# main.net
KiCad netlist of a schematic drawn in EAGLE
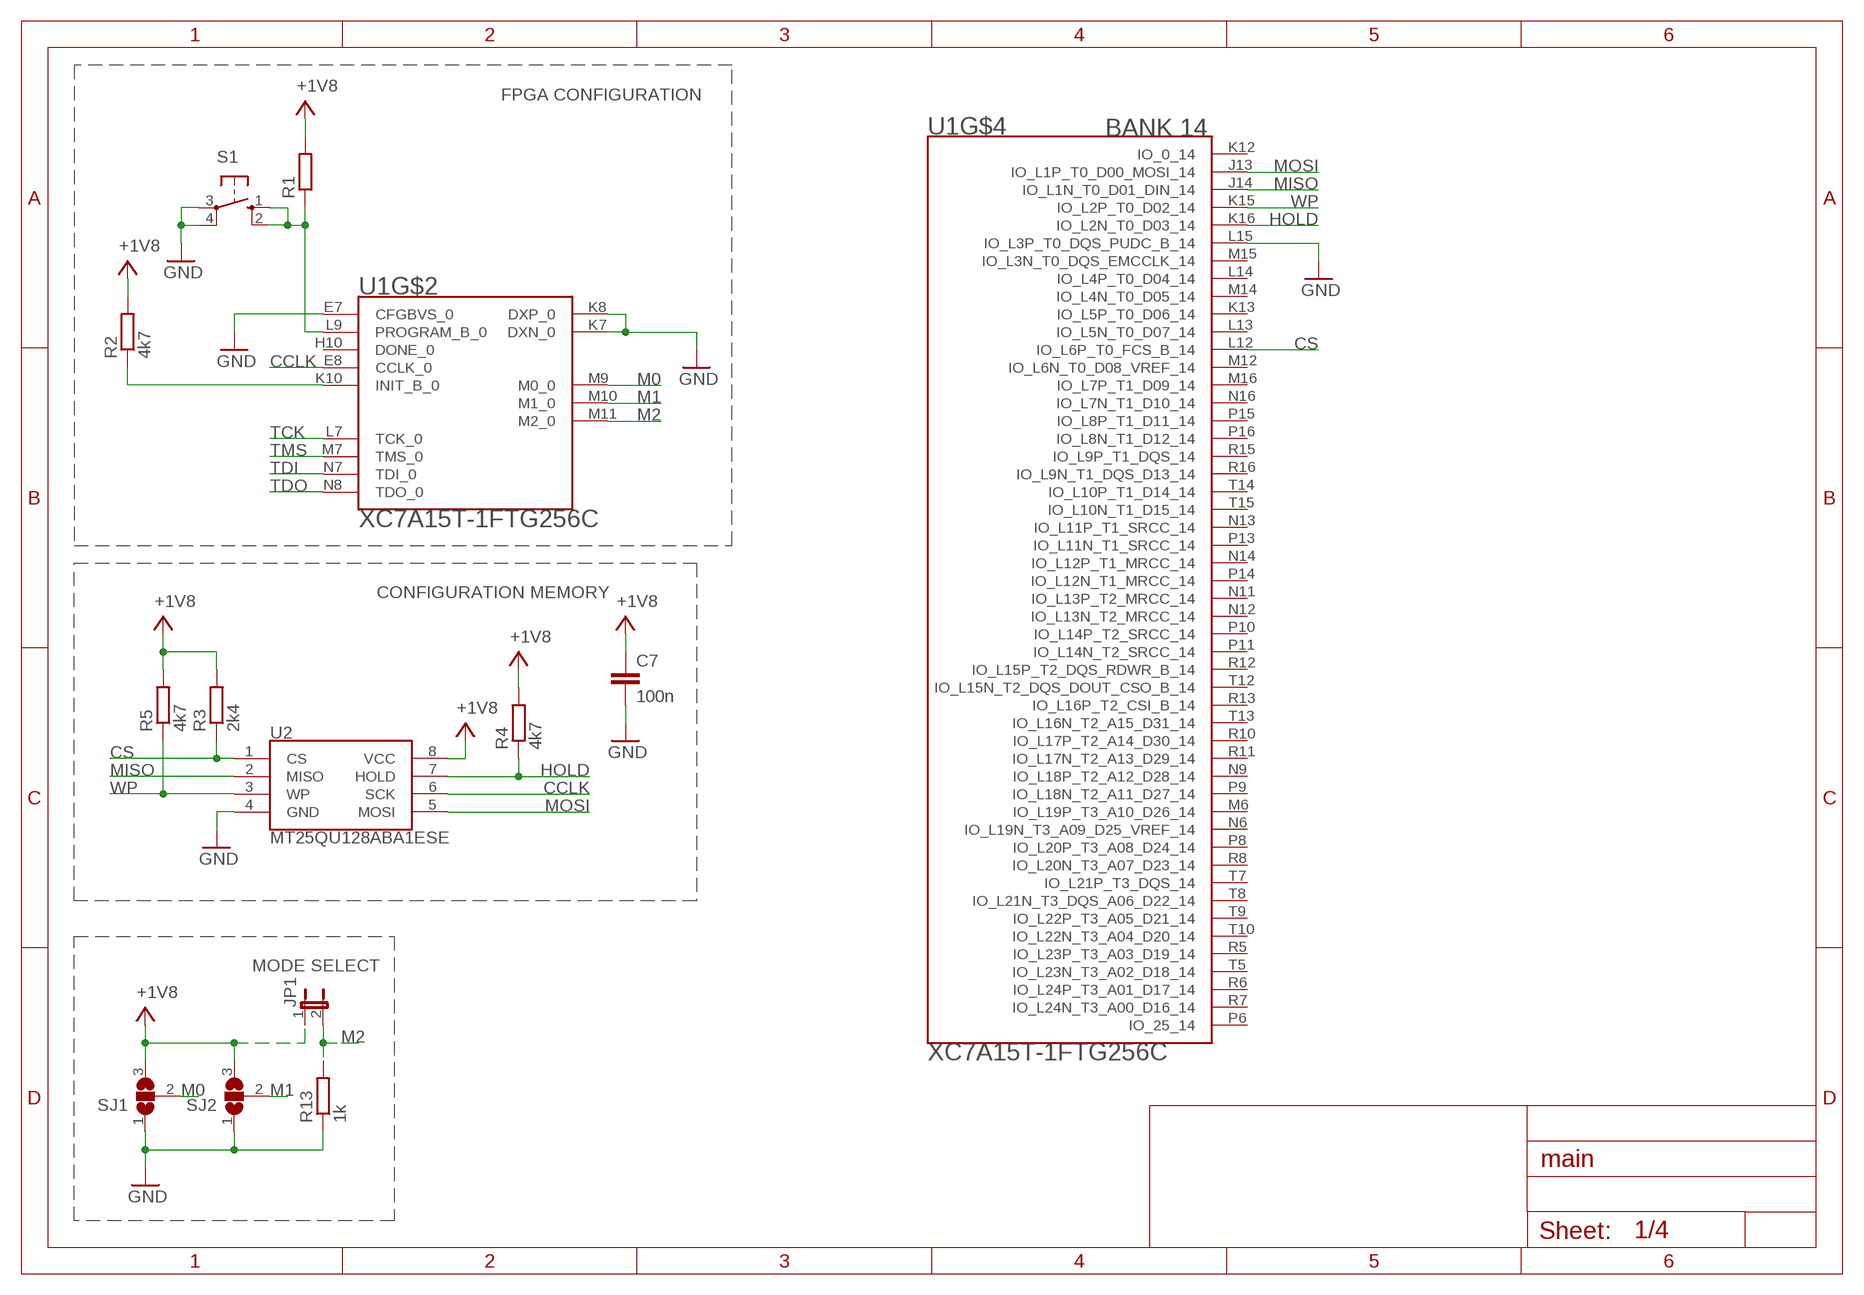
[diagram p0: schematic, sheet 1]
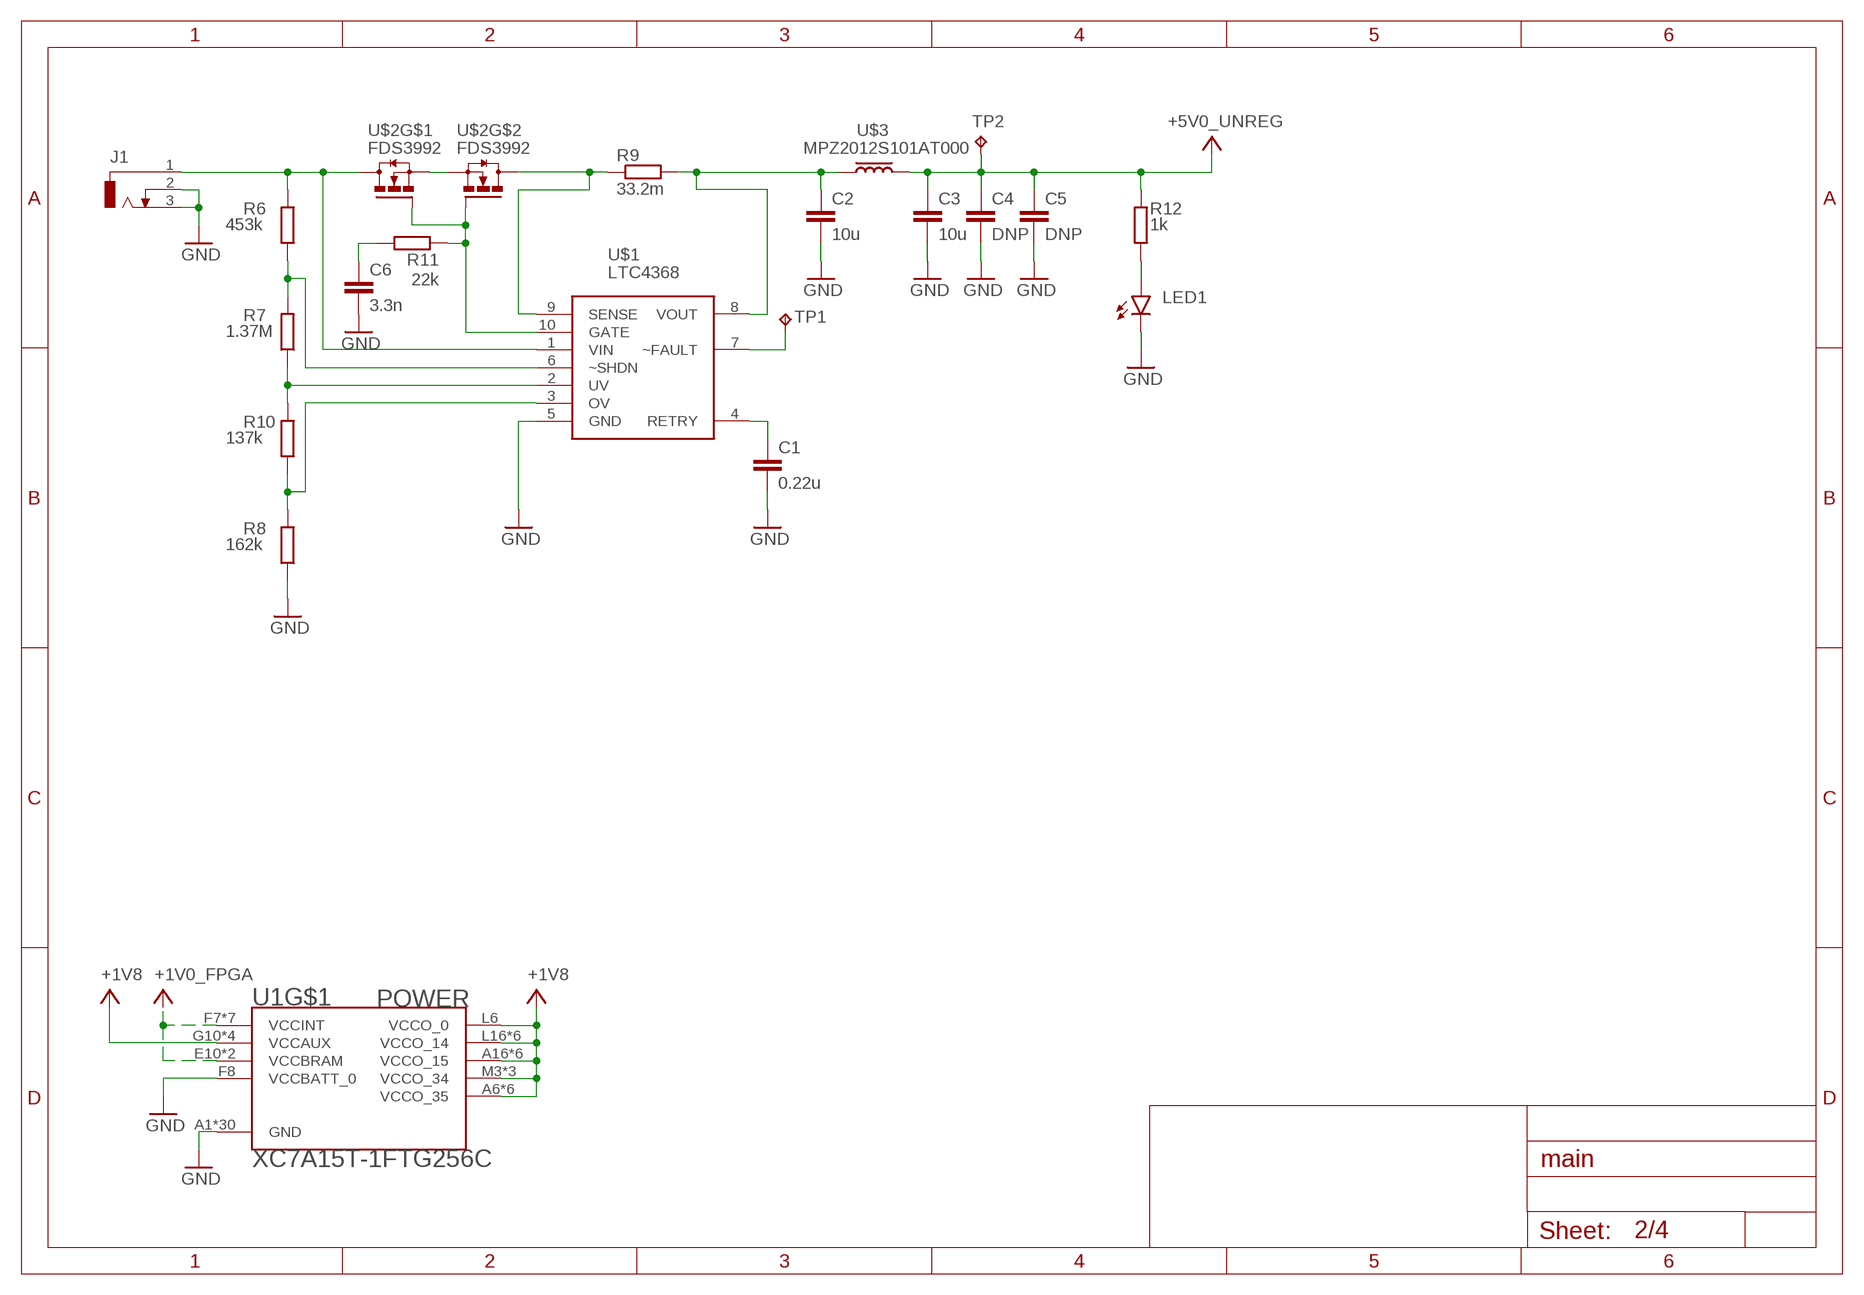
[diagram p1: schematic, sheet 2]
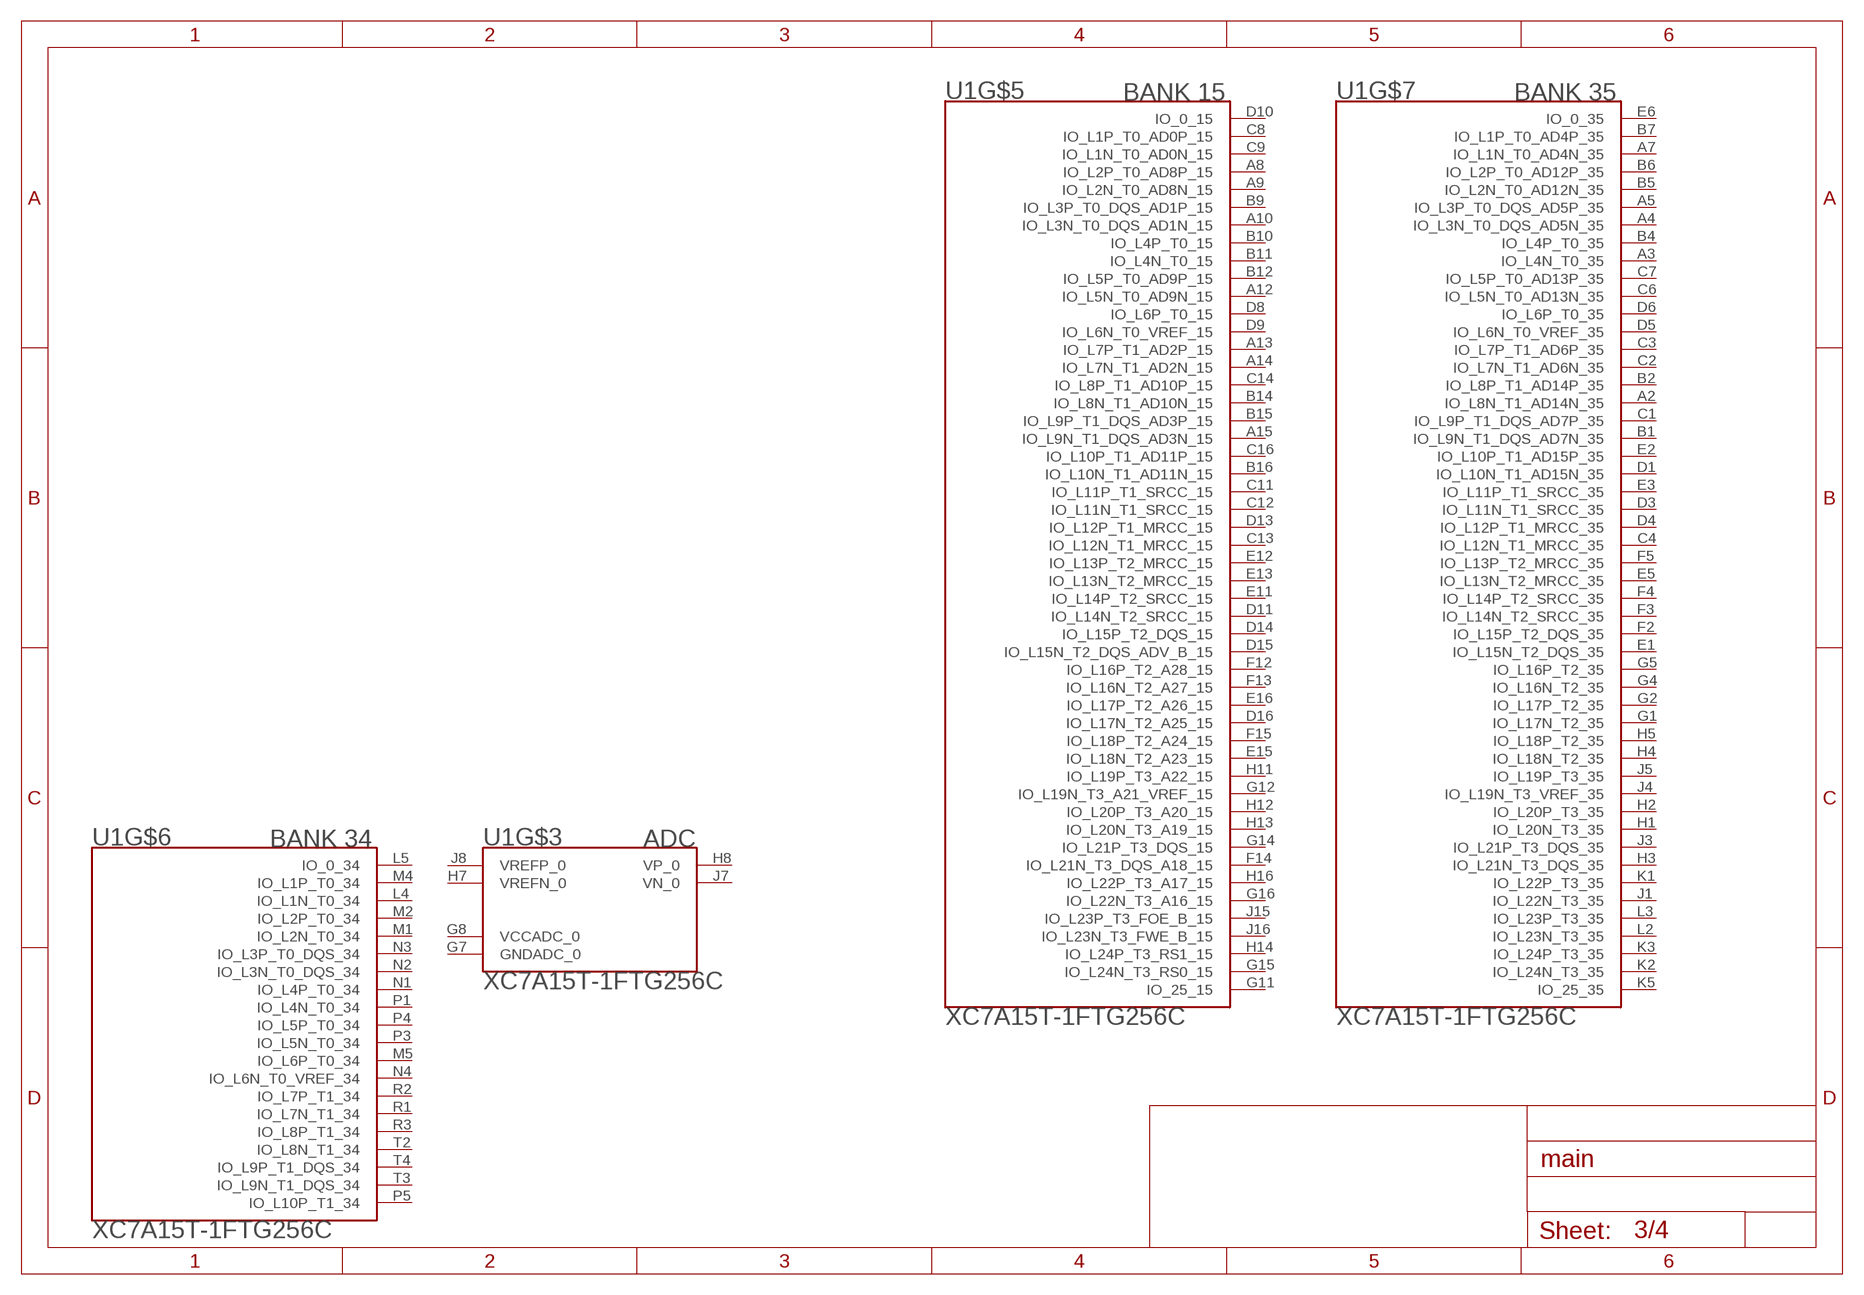
[diagram p2: schematic, sheet 3]
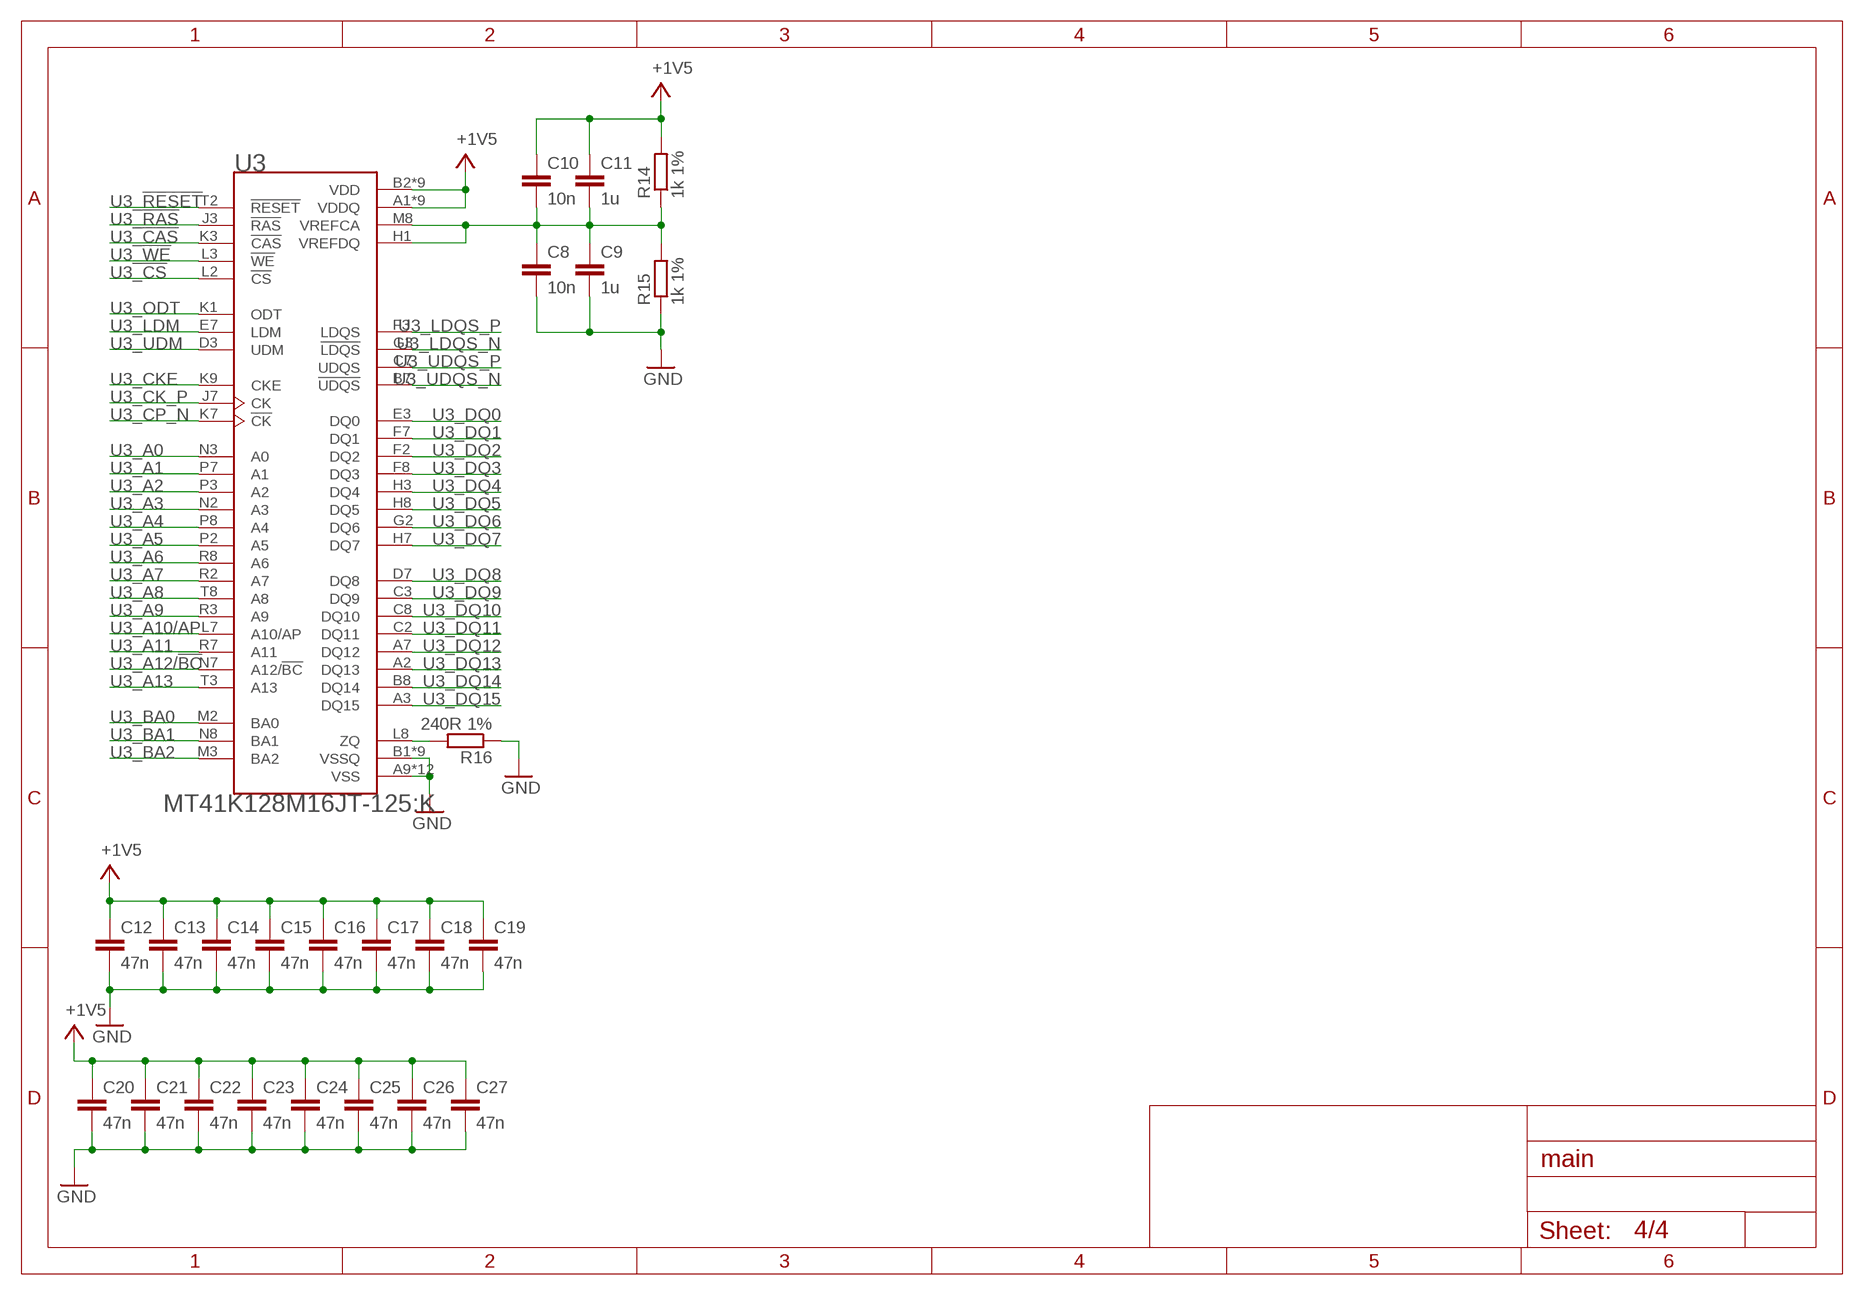
[diagram p3: schematic, sheet 4]

(export (version "E")
  (design (tool "Eeschema 10.0.6"))
  (components
    (comp (ref "C7")
      (value "100n")
      (footprint "eagle-import:C0603")
      (libsource (lib "eagle-import") (part "C-EUC0603"))
    )
    (comp (ref "JP1")
      (value "JP1E")
      (footprint "eagle-import:JP1")
      (libsource (lib "eagle-import") (part "JP1E"))
    )
    (comp (ref "R1")
      (value "R-EU_R0603")
      (footprint "eagle-import:R0603")
      (libsource (lib "eagle-import") (part "R-EU_R0603"))
    )
    (comp (ref "R2")
      (value "4k7")
      (footprint "eagle-import:R0603")
      (libsource (lib "eagle-import") (part "R-EU_R0603"))
    )
    (comp (ref "R3")
      (value "2k4")
      (footprint "eagle-import:R0603")
      (libsource (lib "eagle-import") (part "R-EU_R0603"))
    )
    (comp (ref "R4")
      (value "4k7")
      (footprint "eagle-import:R0603")
      (libsource (lib "eagle-import") (part "R-EU_R0603"))
    )
    (comp (ref "R5")
      (value "4k7")
      (footprint "eagle-import:R0603")
      (libsource (lib "eagle-import") (part "R-EU_R0603"))
    )
    (comp (ref "R13")
      (value "1k")
      (footprint "eagle-import:R0603")
      (libsource (lib "eagle-import") (part "R-EU_R0603"))
    )
    (comp (ref "S1")
      (value "10-XX")
      (footprint "eagle-import:B3F-10XX")
      (fields (field (name "MPN") "B3F-1000"))
      (libsource (lib "eagle-import") (part "10-XX"))
    )
    (comp (ref "SJ1")
      (value "SJ2W")
      (footprint "eagle-import:SJ_2")
      (libsource (lib "eagle-import") (part "SJ2W"))
    )
    (comp (ref "SJ2")
      (value "SJ2W")
      (footprint "eagle-import:SJ_2")
      (libsource (lib "eagle-import") (part "SJ2W"))
    )
    (comp (ref "U1")
      (value "XC7A15T-1FTG256C")
      (footprint "eagle-import:BGA256C100P16X16_1700X1700X155")
      (fields (field (name "MF") "Xilinx Inc."))
      (libsource (lib "eagle-import") (part "XC7A15T-1FTG256C"))
    )
    (comp (ref "U2")
      (value "MT25QU128ABA1ESE")
      (footprint "eagle-import:SO08-EIAJ")
      (libsource (lib "eagle-import") (part "SPI_FLASH-X25XXSMD1"))
    )
    (comp (ref "C8")
      (value "10n")
      (footprint "eagle-import:C0603")
      (libsource (lib "eagle-import") (part "C-EUC0603"))
    )
    (comp (ref "C9")
      (value "1u")
      (footprint "eagle-import:C0603")
      (libsource (lib "eagle-import") (part "C-EUC0603"))
    )
    (comp (ref "C10")
      (value "10n")
      (footprint "eagle-import:C0603")
      (libsource (lib "eagle-import") (part "C-EUC0603"))
    )
    (comp (ref "C11")
      (value "1u")
      (footprint "eagle-import:C0603")
      (libsource (lib "eagle-import") (part "C-EUC0603"))
    )
    (comp (ref "C12")
      (value "47n")
      (footprint "eagle-import:C0603")
      (libsource (lib "eagle-import") (part "C-EUC0603"))
    )
    (comp (ref "C13")
      (value "47n")
      (footprint "eagle-import:C0603")
      (libsource (lib "eagle-import") (part "C-EUC0603"))
    )
    (comp (ref "C14")
      (value "47n")
      (footprint "eagle-import:C0603")
      (libsource (lib "eagle-import") (part "C-EUC0603"))
    )
    (comp (ref "C15")
      (value "47n")
      (footprint "eagle-import:C0603")
      (libsource (lib "eagle-import") (part "C-EUC0603"))
    )
    (comp (ref "C16")
      (value "47n")
      (footprint "eagle-import:C0603")
      (libsource (lib "eagle-import") (part "C-EUC0603"))
    )
    (comp (ref "C17")
      (value "47n")
      (footprint "eagle-import:C0603")
      (libsource (lib "eagle-import") (part "C-EUC0603"))
    )
    (comp (ref "C18")
      (value "47n")
      (footprint "eagle-import:C0603")
      (libsource (lib "eagle-import") (part "C-EUC0603"))
    )
    (comp (ref "C19")
      (value "47n")
      (footprint "eagle-import:C0603")
      (libsource (lib "eagle-import") (part "C-EUC0603"))
    )
    (comp (ref "C20")
      (value "47n")
      (footprint "eagle-import:C0603")
      (libsource (lib "eagle-import") (part "C-EUC0603"))
    )
    (comp (ref "C21")
      (value "47n")
      (footprint "eagle-import:C0603")
      (libsource (lib "eagle-import") (part "C-EUC0603"))
    )
    (comp (ref "C22")
      (value "47n")
      (footprint "eagle-import:C0603")
      (libsource (lib "eagle-import") (part "C-EUC0603"))
    )
    (comp (ref "C23")
      (value "47n")
      (footprint "eagle-import:C0603")
      (libsource (lib "eagle-import") (part "C-EUC0603"))
    )
    (comp (ref "C24")
      (value "47n")
      (footprint "eagle-import:C0603")
      (libsource (lib "eagle-import") (part "C-EUC0603"))
    )
    (comp (ref "C25")
      (value "47n")
      (footprint "eagle-import:C0603")
      (libsource (lib "eagle-import") (part "C-EUC0603"))
    )
    (comp (ref "C26")
      (value "47n")
      (footprint "eagle-import:C0603")
      (libsource (lib "eagle-import") (part "C-EUC0603"))
    )
    (comp (ref "C27")
      (value "47n")
      (footprint "eagle-import:C0603")
      (libsource (lib "eagle-import") (part "C-EUC0603"))
    )
    (comp (ref "R14")
      (value "1k 1%")
      (footprint "eagle-import:R0603")
      (libsource (lib "eagle-import") (part "R-EU_R0603"))
    )
    (comp (ref "R15")
      (value "1k 1%")
      (footprint "eagle-import:R0603")
      (libsource (lib "eagle-import") (part "R-EU_R0603"))
    )
    (comp (ref "R16")
      (value "240R 1%")
      (footprint "eagle-import:R0603")
      (libsource (lib "eagle-import") (part "R-EU_R0603"))
    )
    (comp (ref "U3")
      (value "MT41K128M16JT-125:K")
      (footprint "eagle-import:BGA80P96C6X16_800X1400X110")
      (fields (field (name "MF") "Micron Technology"))
      (libsource (lib "eagle-import") (part "MT41K128M16JT-125{colon}K"))
    )
    (comp (ref "C1")
      (value "0.22u")
      (footprint "eagle-import:C0805")
      (libsource (lib "eagle-import") (part "C-EUC0805"))
    )
    (comp (ref "C2")
      (value "10u")
      (footprint "eagle-import:C0805")
      (libsource (lib "eagle-import") (part "C-EUC0805"))
    )
    (comp (ref "C3")
      (value "10u")
      (footprint "eagle-import:C0805")
      (libsource (lib "eagle-import") (part "C-EUC0805"))
    )
    (comp (ref "C4")
      (value "DNP")
      (footprint "eagle-import:C0805")
      (libsource (lib "eagle-import") (part "C-EUC0805"))
    )
    (comp (ref "C5")
      (value "DNP")
      (footprint "eagle-import:C0805")
      (libsource (lib "eagle-import") (part "C-EUC0805"))
    )
    (comp (ref "C6")
      (value "3.3n")
      (footprint "eagle-import:C0805")
      (libsource (lib "eagle-import") (part "C-EUC0805"))
    )
    (comp (ref "J1")
      (value "DCJ0303")
      (footprint "eagle-import:DCJ0303")
      (libsource (lib "eagle-import") (part "DCJ0303"))
    )
    (comp (ref "LED1")
      (value "LEDCHIP-LED0805")
      (footprint "eagle-import:CHIP-LED0805")
      (libsource (lib "eagle-import") (part "LEDCHIP-LED0805"))
    )
    (comp (ref "R6")
      (value "453k")
      (footprint "eagle-import:R0805")
      (libsource (lib "eagle-import") (part "R-EU_R0805"))
    )
    (comp (ref "R7")
      (value "1.37M")
      (footprint "eagle-import:R0805")
      (libsource (lib "eagle-import") (part "R-EU_R0805"))
    )
    (comp (ref "R8")
      (value "162k")
      (footprint "eagle-import:R0805")
      (libsource (lib "eagle-import") (part "R-EU_R0805"))
    )
    (comp (ref "R9")
      (value "33.2m")
      (footprint "eagle-import:R0805")
      (libsource (lib "eagle-import") (part "R-EU_R0805"))
    )
    (comp (ref "R10")
      (value "137k")
      (footprint "eagle-import:R0805")
      (libsource (lib "eagle-import") (part "R-EU_R0805"))
    )
    (comp (ref "R11")
      (value "22k")
      (footprint "eagle-import:R0805")
      (libsource (lib "eagle-import") (part "R-EU_R0805"))
    )
    (comp (ref "R12")
      (value "1k")
      (footprint "eagle-import:R0805")
      (libsource (lib "eagle-import") (part "R-EU_R0805"))
    )
    (comp (ref "TP1")
      (value "TPB1,27")
      (footprint "eagle-import:B1,27")
      (libsource (lib "eagle-import") (part "TPB1,27"))
    )
    (comp (ref "TP2")
      (value "TPB1,27")
      (footprint "eagle-import:B1,27")
      (libsource (lib "eagle-import") (part "TPB1,27"))
    )
    (comp (ref "U$1")
      (value "LTC4368")
      (footprint "eagle-import:MSOP10")
      (libsource (lib "eagle-import") (part "LTC4368"))
    )
    (comp (ref "U$2")
      (value "FDS3992")
      (footprint "eagle-import:SO-08")
      (libsource (lib "eagle-import") (part "FDS3992"))
    )
    (comp (ref "U$3")
      (value "MPZ2012S101AT000")
      (footprint "eagle-import:FB0805")
      (libsource (lib "eagle-import") (part "MPZ2012S101AT000"))
    )
  )
  (nets
    (net (code "1") (name "+1V0_FPGA") (class "Default")
      (node (ref "U1") (pin "E10") (pinfunction "VCCBRAM_E10") (pintype "power_in"))
      (node (ref "U1") (pin "F11") (pinfunction "VCCBRAM_F11") (pintype "power_in"))
      (node (ref "U1") (pin "F7") (pinfunction "VCCINT_F7") (pintype "power_in"))
      (node (ref "U1") (pin "F9") (pinfunction "VCCINT_F9") (pintype "power_in"))
      (node (ref "U1") (pin "G6") (pinfunction "VCCINT_G6") (pintype "power_in"))
      (node (ref "U1") (pin "H9") (pinfunction "VCCINT_H9") (pintype "power_in"))
      (node (ref "U1") (pin "J6") (pinfunction "VCCINT_J6") (pintype "power_in"))
      (node (ref "U1") (pin "K9") (pinfunction "VCCINT_K9") (pintype "power_in"))
      (node (ref "U1") (pin "L8") (pinfunction "VCCINT_L8") (pintype "power_in"))
    )
    (net (code "2") (name "+1V5") (class "Default")
      (node (ref "C10") (pin "1") (pinfunction "1_1") (pintype "passive"))
      (node (ref "C11") (pin "1") (pinfunction "1_1") (pintype "passive"))
      (node (ref "C12") (pin "1") (pinfunction "1_1") (pintype "passive"))
      (node (ref "C13") (pin "1") (pinfunction "1_1") (pintype "passive"))
      (node (ref "C14") (pin "1") (pinfunction "1_1") (pintype "passive"))
      (node (ref "C15") (pin "1") (pinfunction "1_1") (pintype "passive"))
      (node (ref "C16") (pin "1") (pinfunction "1_1") (pintype "passive"))
      (node (ref "C17") (pin "1") (pinfunction "1_1") (pintype "passive"))
      (node (ref "C18") (pin "1") (pinfunction "1_1") (pintype "passive"))
      (node (ref "C19") (pin "1") (pinfunction "1_1") (pintype "passive"))
      (node (ref "C20") (pin "1") (pinfunction "1_1") (pintype "passive"))
      (node (ref "C21") (pin "1") (pinfunction "1_1") (pintype "passive"))
      (node (ref "C22") (pin "1") (pinfunction "1_1") (pintype "passive"))
      (node (ref "C23") (pin "1") (pinfunction "1_1") (pintype "passive"))
      (node (ref "C24") (pin "1") (pinfunction "1_1") (pintype "passive"))
      (node (ref "C25") (pin "1") (pinfunction "1_1") (pintype "passive"))
      (node (ref "C26") (pin "1") (pinfunction "1_1") (pintype "passive"))
      (node (ref "C27") (pin "1") (pinfunction "1_1") (pintype "passive"))
      (node (ref "R14") (pin "2") (pinfunction "2_2") (pintype "passive"))
      (node (ref "U3") (pin "A1") (pinfunction "VDDQ_A1") (pintype "power_in"))
      (node (ref "U3") (pin "A8") (pinfunction "VDDQ_A8") (pintype "power_in"))
      (node (ref "U3") (pin "B2") (pinfunction "VDD_B2") (pintype "power_in"))
      (node (ref "U3") (pin "C1") (pinfunction "VDDQ_C1") (pintype "power_in"))
      (node (ref "U3") (pin "C9") (pinfunction "VDDQ_C9") (pintype "power_in"))
      (node (ref "U3") (pin "D2") (pinfunction "VDDQ_D2") (pintype "power_in"))
      (node (ref "U3") (pin "D9") (pinfunction "VDD_D9") (pintype "power_in"))
      (node (ref "U3") (pin "E9") (pinfunction "VDDQ_E9") (pintype "power_in"))
      (node (ref "U3") (pin "F1") (pinfunction "VDDQ_F1") (pintype "power_in"))
      (node (ref "U3") (pin "G7") (pinfunction "VDD_G7") (pintype "power_in"))
      (node (ref "U3") (pin "H2") (pinfunction "VDDQ_H2") (pintype "power_in"))
      (node (ref "U3") (pin "H9") (pinfunction "VDDQ_H9") (pintype "power_in"))
      (node (ref "U3") (pin "K2") (pinfunction "VDD_K2") (pintype "power_in"))
      (node (ref "U3") (pin "K8") (pinfunction "VDD_K8") (pintype "power_in"))
      (node (ref "U3") (pin "N1") (pinfunction "VDD_N1") (pintype "power_in"))
      (node (ref "U3") (pin "N9") (pinfunction "VDD_N9") (pintype "power_in"))
      (node (ref "U3") (pin "R1") (pinfunction "VDD_R1") (pintype "power_in"))
      (node (ref "U3") (pin "R9") (pinfunction "VDD_R9") (pintype "power_in"))
    )
    (net (code "3") (name "+1V8") (class "Default")
      (node (ref "C7") (pin "1") (pinfunction "1_1") (pintype "passive"))
      (node (ref "JP1") (pin "1") (pinfunction "1_1") (pintype "passive"))
      (node (ref "R1") (pin "2") (pinfunction "2_2") (pintype "passive"))
      (node (ref "R2") (pin "2") (pinfunction "2_2") (pintype "passive"))
      (node (ref "R3") (pin "2") (pinfunction "2_2") (pintype "passive"))
      (node (ref "R4") (pin "2") (pinfunction "2_2") (pintype "passive"))
      (node (ref "R5") (pin "2") (pinfunction "2_2") (pintype "passive"))
      (node (ref "SJ1") (pin "3") (pinfunction "3_3") (pintype "passive"))
      (node (ref "SJ2") (pin "3") (pinfunction "3_3") (pintype "passive"))
      (node (ref "U1") (pin "A16") (pinfunction "VCCO_15_A16") (pintype "power_in"))
      (node (ref "U1") (pin "A6") (pinfunction "VCCO_35_A6") (pintype "power_in"))
      (node (ref "U1") (pin "B13") (pinfunction "VCCO_15_B13") (pintype "power_in"))
      (node (ref "U1") (pin "B3") (pinfunction "VCCO_35_B3") (pintype "power_in"))
      (node (ref "U1") (pin "C10") (pinfunction "VCCO_15_C10") (pintype "power_in"))
      (node (ref "U1") (pin "D7") (pinfunction "VCCO_35_D7") (pintype "power_in"))
      (node (ref "U1") (pin "E14") (pinfunction "VCCO_15_E14") (pintype "power_in"))
      (node (ref "U1") (pin "E4") (pinfunction "VCCO_35_E4") (pintype "power_in"))
      (node (ref "U1") (pin "F1") (pinfunction "VCCO_35_F1") (pintype "power_in"))
      (node (ref "U1") (pin "G10") (pinfunction "VCCAUX_G10") (pintype "power_in"))
      (node (ref "U1") (pin "H15") (pinfunction "VCCO_15_H15") (pintype "power_in"))
      (node (ref "U1") (pin "J10") (pinfunction "VCCAUX_J10") (pintype "power_in"))
      (node (ref "U1") (pin "J12") (pinfunction "VCCO_15_J12") (pintype "power_in"))
      (node (ref "U1") (pin "J2") (pinfunction "VCCO_35_J2") (pintype "power_in"))
      (node (ref "U1") (pin "K11") (pinfunction "VCCAUX_K11") (pintype "power_in"))
      (node (ref "U1") (pin "L10") (pinfunction "VCCAUX_L10") (pintype "power_in"))
      (node (ref "U1") (pin "L16") (pinfunction "VCCO_14_L16") (pintype "power_in"))
      (node (ref "U1") (pin "L6") (pinfunction "VCCO_0_L6") (pintype "power_in"))
      (node (ref "U1") (pin "M13") (pinfunction "VCCO_14_M13") (pintype "power_in"))
      (node (ref "U1") (pin "M3") (pinfunction "VCCO_34_M3") (pintype "power_in"))
      (node (ref "U1") (pin "N10") (pinfunction "VCCO_14_N10") (pintype "power_in"))
      (node (ref "U1") (pin "P7") (pinfunction "VCCO_14_P7") (pintype "power_in"))
      (node (ref "U1") (pin "R14") (pinfunction "VCCO_14_R14") (pintype "power_in"))
      (node (ref "U1") (pin "R4") (pinfunction "VCCO_34_R4") (pintype "power_in"))
      (node (ref "U1") (pin "T1") (pinfunction "VCCO_34_T1") (pintype "power_in"))
      (node (ref "U1") (pin "T11") (pinfunction "VCCO_14_T11") (pintype "power_in"))
      (node (ref "U2") (pin "8") (pinfunction "VCC_8") (pintype "power_in"))
    )
    (net (code "4") (name "+5V0_UNREG") (class "Default")
      (node (ref "C3") (pin "1") (pinfunction "1_1") (pintype "passive"))
      (node (ref "C4") (pin "1") (pinfunction "1_1") (pintype "passive"))
      (node (ref "C5") (pin "1") (pinfunction "1_1") (pintype "passive"))
      (node (ref "R12") (pin "2") (pinfunction "2_2") (pintype "passive"))
      (node (ref "TP2") (pin "TP") (pinfunction "TP_TP") (pintype "input"))
      (node (ref "U$3") (pin "2") (pinfunction "2_2") (pintype "passive"))
    )
    (net (code "5") (name "CCLK") (class "Default")
      (node (ref "U1") (pin "E8") (pinfunction "CCLK_0_E8") (pintype "bidirectional"))
      (node (ref "U2") (pin "6") (pinfunction "SCK_6") (pintype "bidirectional"))
    )
    (net (code "6") (name "CS") (class "Default")
      (node (ref "R3") (pin "1") (pinfunction "1_1") (pintype "passive"))
      (node (ref "U1") (pin "L12") (pinfunction "IO_L6P_T0_FCS_B_14_L12") (pintype "bidirectional"))
      (node (ref "U2") (pin "1") (pinfunction "CS_1") (pintype "bidirectional"))
    )
    (net (code "7") (name "GND") (class "Default")
      (node (ref "C1") (pin "2") (pinfunction "2_2") (pintype "passive"))
      (node (ref "C12") (pin "2") (pinfunction "2_2") (pintype "passive"))
      (node (ref "C13") (pin "2") (pinfunction "2_2") (pintype "passive"))
      (node (ref "C14") (pin "2") (pinfunction "2_2") (pintype "passive"))
      (node (ref "C15") (pin "2") (pinfunction "2_2") (pintype "passive"))
      (node (ref "C16") (pin "2") (pinfunction "2_2") (pintype "passive"))
      (node (ref "C17") (pin "2") (pinfunction "2_2") (pintype "passive"))
      (node (ref "C18") (pin "2") (pinfunction "2_2") (pintype "passive"))
      (node (ref "C19") (pin "2") (pinfunction "2_2") (pintype "passive"))
      (node (ref "C2") (pin "2") (pinfunction "2_2") (pintype "passive"))
      (node (ref "C20") (pin "2") (pinfunction "2_2") (pintype "passive"))
      (node (ref "C21") (pin "2") (pinfunction "2_2") (pintype "passive"))
      (node (ref "C22") (pin "2") (pinfunction "2_2") (pintype "passive"))
      (node (ref "C23") (pin "2") (pinfunction "2_2") (pintype "passive"))
      (node (ref "C24") (pin "2") (pinfunction "2_2") (pintype "passive"))
      (node (ref "C25") (pin "2") (pinfunction "2_2") (pintype "passive"))
      (node (ref "C26") (pin "2") (pinfunction "2_2") (pintype "passive"))
      (node (ref "C27") (pin "2") (pinfunction "2_2") (pintype "passive"))
      (node (ref "C3") (pin "2") (pinfunction "2_2") (pintype "passive"))
      (node (ref "C4") (pin "2") (pinfunction "2_2") (pintype "passive"))
      (node (ref "C5") (pin "2") (pinfunction "2_2") (pintype "passive"))
      (node (ref "C6") (pin "2") (pinfunction "2_2") (pintype "passive"))
      (node (ref "C7") (pin "2") (pinfunction "2_2") (pintype "passive"))
      (node (ref "C8") (pin "2") (pinfunction "2_2") (pintype "passive"))
      (node (ref "C9") (pin "2") (pinfunction "2_2") (pintype "passive"))
      (node (ref "J1") (pin "2") (pinfunction "2_2") (pintype "passive"))
      (node (ref "J1") (pin "3") (pinfunction "3_3") (pintype "passive"))
      (node (ref "LED1") (pin "C") (pinfunction "C_C") (pintype "passive"))
      (node (ref "R13") (pin "1") (pinfunction "1_1") (pintype "passive"))
      (node (ref "R15") (pin "1") (pinfunction "1_1") (pintype "passive"))
      (node (ref "R16") (pin "1") (pinfunction "1_1") (pintype "passive"))
      (node (ref "R8") (pin "1") (pinfunction "1_1") (pintype "passive"))
      (node (ref "S1") (pin "3") (pinfunction "P_3") (pintype "passive"))
      (node (ref "S1") (pin "4") (pinfunction "P1_4") (pintype "passive"))
      (node (ref "SJ1") (pin "1") (pinfunction "1_1") (pintype "passive"))
      (node (ref "SJ2") (pin "1") (pinfunction "1_1") (pintype "passive"))
      (node (ref "U$1") (pin "5") (pinfunction "GND_5") (pintype "bidirectional"))
      (node (ref "U1") (pin "A1") (pinfunction "GND_A1") (pintype "power_in"))
      (node (ref "U1") (pin "A11") (pinfunction "GND_A11") (pintype "power_in"))
      (node (ref "U1") (pin "B8") (pinfunction "GND_B8") (pintype "power_in"))
      (node (ref "U1") (pin "C15") (pinfunction "GND_C15") (pintype "power_in"))
      (node (ref "U1") (pin "C5") (pinfunction "GND_C5") (pintype "power_in"))
      (node (ref "U1") (pin "D12") (pinfunction "GND_D12") (pintype "power_in"))
      (node (ref "U1") (pin "D2") (pinfunction "GND_D2") (pintype "power_in"))
      (node (ref "U1") (pin "E7") (pinfunction "CFGBVS_0_E7") (pintype "input"))
      (node (ref "U1") (pin "E9") (pinfunction "GND_E9") (pintype "power_in"))
      (node (ref "U1") (pin "F10") (pinfunction "GND_F10") (pintype "power_in"))
      (node (ref "U1") (pin "F16") (pinfunction "GND_F16") (pintype "power_in"))
      (node (ref "U1") (pin "F6") (pinfunction "GND_F6") (pintype "power_in"))
      (node (ref "U1") (pin "F8") (pinfunction "VCCBATT_0_F8") (pintype "power_in"))
      (node (ref "U1") (pin "G13") (pinfunction "GND_G13") (pintype "power_in"))
      (node (ref "U1") (pin "G3") (pinfunction "GND_G3") (pintype "power_in"))
      (node (ref "U1") (pin "G9") (pinfunction "GND_G9") (pintype "power_in"))
      (node (ref "U1") (pin "H6") (pinfunction "GND_H6") (pintype "power_in"))
      (node (ref "U1") (pin "J11") (pinfunction "GND_J11") (pintype "power_in"))
      (node (ref "U1") (pin "J9") (pinfunction "GND_J9") (pintype "power_in"))
      (node (ref "U1") (pin "K14") (pinfunction "GND_K14") (pintype "power_in"))
      (node (ref "U1") (pin "K4") (pinfunction "GND_K4") (pintype "power_in"))
      (node (ref "U1") (pin "K6") (pinfunction "GND_K6") (pintype "power_in"))
      (node (ref "U1") (pin "K7") (pinfunction "DXN_0_K7") (pintype "input"))
      (node (ref "U1") (pin "K8") (pinfunction "DXP_0_K8") (pintype "input"))
      (node (ref "U1") (pin "L1") (pinfunction "GND_L1") (pintype "power_in"))
      (node (ref "U1") (pin "L11") (pinfunction "GND_L11") (pintype "power_in"))
      (node (ref "U1") (pin "L15") (pinfunction "IO_L3P_T0_DQS_PUDC_B_14_L15") (pintype "bidirectional"))
      (node (ref "U1") (pin "M8") (pinfunction "GND_M8") (pintype "power_in"))
      (node (ref "U1") (pin "N15") (pinfunction "GND_N15") (pintype "power_in"))
      (node (ref "U1") (pin "N5") (pinfunction "GND_N5") (pintype "power_in"))
      (node (ref "U1") (pin "P12") (pinfunction "GND_P12") (pintype "power_in"))
      (node (ref "U1") (pin "P2") (pinfunction "GND_P2") (pintype "power_in"))
      (node (ref "U1") (pin "R9") (pinfunction "GND_R9") (pintype "power_in"))
      (node (ref "U1") (pin "T16") (pinfunction "GND_T16") (pintype "power_in"))
      (node (ref "U1") (pin "T6") (pinfunction "GND_T6") (pintype "power_in"))
      (node (ref "U2") (pin "4") (pinfunction "GND_4") (pintype "power_in"))
      (node (ref "U3") (pin "A9") (pinfunction "VSS_A9") (pintype "passive"))
      (node (ref "U3") (pin "B1") (pinfunction "VSSQ_B1") (pintype "passive"))
      (node (ref "U3") (pin "B3") (pinfunction "VSS_B3") (pintype "passive"))
      (node (ref "U3") (pin "B9") (pinfunction "VSSQ_B9") (pintype "passive"))
      (node (ref "U3") (pin "D1") (pinfunction "VSSQ_D1") (pintype "passive"))
      (node (ref "U3") (pin "D8") (pinfunction "VSSQ_D8") (pintype "passive"))
      (node (ref "U3") (pin "E1") (pinfunction "VSS_E1") (pintype "passive"))
      (node (ref "U3") (pin "E2") (pinfunction "VSSQ_E2") (pintype "passive"))
      (node (ref "U3") (pin "E8") (pinfunction "VSSQ_E8") (pintype "passive"))
      (node (ref "U3") (pin "F9") (pinfunction "VSSQ_F9") (pintype "passive"))
      (node (ref "U3") (pin "G1") (pinfunction "VSSQ_G1") (pintype "passive"))
      (node (ref "U3") (pin "G8") (pinfunction "VSS_G8") (pintype "passive"))
      (node (ref "U3") (pin "G9") (pinfunction "VSSQ_G9") (pintype "passive"))
      (node (ref "U3") (pin "J2") (pinfunction "VSS_J2") (pintype "passive"))
      (node (ref "U3") (pin "J8") (pinfunction "VSS_J8") (pintype "passive"))
      (node (ref "U3") (pin "M1") (pinfunction "VSS_M1") (pintype "passive"))
      (node (ref "U3") (pin "M9") (pinfunction "VSS_M9") (pintype "passive"))
      (node (ref "U3") (pin "P1") (pinfunction "VSS_P1") (pintype "passive"))
      (node (ref "U3") (pin "P9") (pinfunction "VSS_P9") (pintype "passive"))
      (node (ref "U3") (pin "T1") (pinfunction "VSS_T1") (pintype "passive"))
      (node (ref "U3") (pin "T9") (pinfunction "VSS_T9") (pintype "passive"))
    )
    (net (code "8") (name "GNDADC_0") (class "Default")
      (node (ref "U1") (pin "G7") (pinfunction "GNDADC_0_G7") (pintype "power_in"))
    )
    (net (code "9") (name "HOLD") (class "Default")
      (node (ref "R4") (pin "1") (pinfunction "1_1") (pintype "passive"))
      (node (ref "U1") (pin "K16") (pinfunction "IO_L2N_T0_D03_14_K16") (pintype "bidirectional"))
      (node (ref "U2") (pin "7") (pinfunction "HOLD_7") (pintype "bidirectional"))
    )
    (net (code "10") (name "M0") (class "Default")
      (node (ref "SJ1") (pin "2") (pinfunction "2_2") (pintype "passive"))
      (node (ref "U1") (pin "M9") (pinfunction "M0_0_M9") (pintype "input"))
    )
    (net (code "11") (name "M1") (class "Default")
      (node (ref "SJ2") (pin "2") (pinfunction "2_2") (pintype "passive"))
      (node (ref "U1") (pin "M10") (pinfunction "M1_0_M10") (pintype "input"))
    )
    (net (code "12") (name "M2") (class "Default")
      (node (ref "JP1") (pin "2") (pinfunction "2_2") (pintype "passive"))
      (node (ref "R13") (pin "2") (pinfunction "2_2") (pintype "passive"))
      (node (ref "U1") (pin "M11") (pinfunction "M2_0_M11") (pintype "input"))
    )
    (net (code "13") (name "MISO") (class "Default")
      (node (ref "U1") (pin "J14") (pinfunction "IO_L1N_T0_D01_DIN_14_J14") (pintype "bidirectional"))
      (node (ref "U2") (pin "2") (pinfunction "MISO_2") (pintype "bidirectional"))
    )
    (net (code "14") (name "MOSI") (class "Default")
      (node (ref "U1") (pin "J13") (pinfunction "IO_L1P_T0_D00_MOSI_14_J13") (pintype "bidirectional"))
      (node (ref "U2") (pin "5") (pinfunction "MOSI_5") (pintype "bidirectional"))
    )
    (net (code "15") (name "Net-(C6-Pad1)") (class "Default")
      (node (ref "C6") (pin "1") (pinfunction "1_1") (pintype "passive"))
      (node (ref "R11") (pin "2") (pinfunction "2_2") (pintype "passive"))
    )
    (net (code "16") (name "Net-(LED1-PadA)") (class "Default")
      (node (ref "LED1") (pin "A") (pinfunction "A_A") (pintype "passive"))
      (node (ref "R12") (pin "1") (pinfunction "1_1") (pintype "passive"))
    )
    (net (code "17") (name "Net-(S1-S)") (class "Default")
      (node (ref "R1") (pin "1") (pinfunction "1_1") (pintype "passive"))
      (node (ref "S1") (pin "1") (pinfunction "S_1") (pintype "passive"))
      (node (ref "S1") (pin "2") (pinfunction "S1_2") (pintype "passive"))
      (node (ref "U1") (pin "L9") (pinfunction "PROGRAM_B_0_L9") (pintype "input"))
    )
    (net (code "18") (name "Net-(U$1-GATE)") (class "Default")
      (node (ref "R11") (pin "1") (pinfunction "1_1") (pintype "passive"))
      (node (ref "U$1") (pin "10") (pinfunction "GATE_10") (pintype "bidirectional"))
      (node (ref "U$2") (pin "2") (pinfunction "G_2") (pintype "passive"))
      (node (ref "U$2") (pin "4") (pinfunction "G_4") (pintype "passive"))
    )
    (net (code "19") (name "Net-(U$1-OV)") (class "Default")
      (node (ref "R10") (pin "1") (pinfunction "1_1") (pintype "passive"))
      (node (ref "R8") (pin "2") (pinfunction "2_2") (pintype "passive"))
      (node (ref "U$1") (pin "3") (pinfunction "OV_3") (pintype "bidirectional"))
    )
    (net (code "20") (name "Net-(U$1-RETRY)") (class "Default")
      (node (ref "C1") (pin "1") (pinfunction "1_1") (pintype "passive"))
      (node (ref "U$1") (pin "4") (pinfunction "RETRY_4") (pintype "bidirectional"))
    )
    (net (code "21") (name "Net-(U$1-SENSE)") (class "Default")
      (node (ref "R9") (pin "1") (pinfunction "1_1") (pintype "passive"))
      (node (ref "U$1") (pin "9") (pinfunction "SENSE_9") (pintype "bidirectional"))
      (node (ref "U$2") (pin "5") (pinfunction "D_5") (pintype "passive"))
      (node (ref "U$2") (pin "6") (pinfunction "D_6") (pintype "passive"))
    )
    (net (code "22") (name "Net-(U$1-UV)") (class "Default")
      (node (ref "R10") (pin "2") (pinfunction "2_2") (pintype "passive"))
      (node (ref "R7") (pin "1") (pinfunction "1_1") (pintype "passive"))
      (node (ref "U$1") (pin "2") (pinfunction "UV_2") (pintype "bidirectional"))
    )
    (net (code "23") (name "Net-(U$1-VIN)") (class "Default")
      (node (ref "J1") (pin "1") (pinfunction "1_1") (pintype "passive"))
      (node (ref "R6") (pin "2") (pinfunction "2_2") (pintype "passive"))
      (node (ref "U$1") (pin "1") (pinfunction "VIN_1") (pintype "bidirectional"))
      (node (ref "U$2") (pin "7") (pinfunction "D_7") (pintype "passive"))
      (node (ref "U$2") (pin "8") (pinfunction "D_8") (pintype "passive"))
    )
    (net (code "24") (name "Net-(U$1-VOUT)") (class "Default")
      (node (ref "C2") (pin "1") (pinfunction "1_1") (pintype "passive"))
      (node (ref "R9") (pin "2") (pinfunction "2_2") (pintype "passive"))
      (node (ref "U$1") (pin "8") (pinfunction "VOUT_8") (pintype "bidirectional"))
      (node (ref "U$3") (pin "1") (pinfunction "1_1") (pintype "passive"))
    )
    (net (code "25") (name "Net-(U$1-~{FAULT})") (class "Default")
      (node (ref "TP1") (pin "TP") (pinfunction "TP_TP") (pintype "input"))
      (node (ref "U$1") (pin "7") (pinfunction "~{FAULT}_7") (pintype "bidirectional"))
    )
    (net (code "26") (name "Net-(U$1-~{SHDN})") (class "Default")
      (node (ref "R6") (pin "1") (pinfunction "1_1") (pintype "passive"))
      (node (ref "R7") (pin "2") (pinfunction "2_2") (pintype "passive"))
      (node (ref "U$1") (pin "6") (pinfunction "~{SHDN}_6") (pintype "bidirectional"))
    )
    (net (code "27") (name "Net-(U$2A-S)") (class "Default")
      (node (ref "U$2") (pin "1") (pinfunction "S_1") (pintype "passive"))
      (node (ref "U$2") (pin "3") (pinfunction "S_3") (pintype "passive"))
    )
    (net (code "28") (name "Net-(U1B-INIT_B_0)") (class "Default")
      (node (ref "R2") (pin "1") (pinfunction "1_1") (pintype "passive"))
      (node (ref "U1") (pin "K10") (pinfunction "INIT_B_0_K10") (pintype "bidirectional"))
    )
    (net (code "29") (name "Net-(U3-VREFCA)") (class "Default")
      (node (ref "C10") (pin "2") (pinfunction "2_2") (pintype "passive"))
      (node (ref "C11") (pin "2") (pinfunction "2_2") (pintype "passive"))
      (node (ref "C8") (pin "1") (pinfunction "1_1") (pintype "passive"))
      (node (ref "C9") (pin "1") (pinfunction "1_1") (pintype "passive"))
      (node (ref "R14") (pin "1") (pinfunction "1_1") (pintype "passive"))
      (node (ref "R15") (pin "2") (pinfunction "2_2") (pintype "passive"))
      (node (ref "U3") (pin "H1") (pinfunction "VREFDQ_H1") (pintype "power_in"))
      (node (ref "U3") (pin "M8") (pinfunction "VREFCA_M8") (pintype "power_in"))
    )
    (net (code "30") (name "Net-(U3-ZQ)") (class "Default")
      (node (ref "R16") (pin "2") (pinfunction "2_2") (pintype "passive"))
      (node (ref "U3") (pin "L8") (pinfunction "ZQ_L8") (pintype "passive"))
    )
    (net (code "31") (name "TCK") (class "Default")
      (node (ref "U1") (pin "L7") (pinfunction "TCK_0_L7") (pintype "input"))
    )
    (net (code "32") (name "TDI") (class "Default")
      (node (ref "U1") (pin "N7") (pinfunction "TDI_0_N7") (pintype "input"))
    )
    (net (code "33") (name "TDO") (class "Default")
      (node (ref "U1") (pin "N8") (pinfunction "TDO_0_N8") (pintype "output"))
    )
    (net (code "34") (name "TMS") (class "Default")
      (node (ref "U1") (pin "M7") (pinfunction "TMS_0_M7") (pintype "input"))
    )
    (net (code "35") (name "U3_A0") (class "Default")
      (node (ref "U3") (pin "N3") (pinfunction "A0_N3") (pintype "input"))
    )
    (net (code "36") (name "U3_A1") (class "Default")
      (node (ref "U3") (pin "P7") (pinfunction "A1_P7") (pintype "input"))
    )
    (net (code "37") (name "U3_A2") (class "Default")
      (node (ref "U3") (pin "P3") (pinfunction "A2_P3") (pintype "input"))
    )
    (net (code "38") (name "U3_A3") (class "Default")
      (node (ref "U3") (pin "N2") (pinfunction "A3_N2") (pintype "input"))
    )
    (net (code "39") (name "U3_A4") (class "Default")
      (node (ref "U3") (pin "P8") (pinfunction "A4_P8") (pintype "input"))
    )
    (net (code "40") (name "U3_A5") (class "Default")
      (node (ref "U3") (pin "P2") (pinfunction "A5_P2") (pintype "input"))
    )
    (net (code "41") (name "U3_A6") (class "Default")
      (node (ref "U3") (pin "R8") (pinfunction "A6_R8") (pintype "input"))
    )
    (net (code "42") (name "U3_A7") (class "Default")
      (node (ref "U3") (pin "R2") (pinfunction "A7_R2") (pintype "input"))
    )
    (net (code "43") (name "U3_A8") (class "Default")
      (node (ref "U3") (pin "T8") (pinfunction "A8_T8") (pintype "input"))
    )
    (net (code "44") (name "U3_A9") (class "Default")
      (node (ref "U3") (pin "R3") (pinfunction "A9_R3") (pintype "input"))
    )
    (net (code "45") (name "U3_A10{slash}AP") (class "Default")
      (node (ref "U3") (pin "L7") (pinfunction "A10/AP_L7") (pintype "input"))
    )
    (net (code "46") (name "U3_A11") (class "Default")
      (node (ref "U3") (pin "R7") (pinfunction "A11_R7") (pintype "input"))
    )
    (net (code "47") (name "U3_A12{slash}~{BC}") (class "Default")
      (node (ref "U3") (pin "N7") (pinfunction "A12/~{BC}_N7") (pintype "input"))
    )
    (net (code "48") (name "U3_A13") (class "Default")
      (node (ref "U3") (pin "T3") (pinfunction "A13_T3") (pintype "input"))
    )
    (net (code "49") (name "U3_BA0") (class "Default")
      (node (ref "U3") (pin "M2") (pinfunction "BA0_M2") (pintype "input"))
    )
    (net (code "50") (name "U3_BA1") (class "Default")
      (node (ref "U3") (pin "N8") (pinfunction "BA1_N8") (pintype "input"))
    )
    (net (code "51") (name "U3_BA2") (class "Default")
      (node (ref "U3") (pin "M3") (pinfunction "BA2_M3") (pintype "input"))
    )
    (net (code "52") (name "U3_CKE") (class "Default")
      (node (ref "U3") (pin "K9") (pinfunction "CKE_K9") (pintype "input"))
    )
    (net (code "53") (name "U3_CK_P") (class "Default")
      (node (ref "U3") (pin "J7") (pinfunction "CK_J7") (pintype "input"))
    )
    (net (code "54") (name "U3_CP_N") (class "Default")
      (node (ref "U3") (pin "K7") (pinfunction "~{CK}_K7") (pintype "input"))
    )
    (net (code "55") (name "U3_DQ0") (class "Default")
      (node (ref "U3") (pin "E3") (pinfunction "DQ0_E3") (pintype "bidirectional"))
    )
    (net (code "56") (name "U3_DQ1") (class "Default")
      (node (ref "U3") (pin "F7") (pinfunction "DQ1_F7") (pintype "bidirectional"))
    )
    (net (code "57") (name "U3_DQ2") (class "Default")
      (node (ref "U3") (pin "F2") (pinfunction "DQ2_F2") (pintype "bidirectional"))
    )
    (net (code "58") (name "U3_DQ3") (class "Default")
      (node (ref "U3") (pin "F8") (pinfunction "DQ3_F8") (pintype "bidirectional"))
    )
    (net (code "59") (name "U3_DQ4") (class "Default")
      (node (ref "U3") (pin "H3") (pinfunction "DQ4_H3") (pintype "bidirectional"))
    )
    (net (code "60") (name "U3_DQ5") (class "Default")
      (node (ref "U3") (pin "H8") (pinfunction "DQ5_H8") (pintype "bidirectional"))
    )
    (net (code "61") (name "U3_DQ6") (class "Default")
      (node (ref "U3") (pin "G2") (pinfunction "DQ6_G2") (pintype "bidirectional"))
    )
    (net (code "62") (name "U3_DQ7") (class "Default")
      (node (ref "U3") (pin "H7") (pinfunction "DQ7_H7") (pintype "bidirectional"))
    )
    (net (code "63") (name "U3_DQ8") (class "Default")
      (node (ref "U3") (pin "D7") (pinfunction "DQ8_D7") (pintype "bidirectional"))
    )
    (net (code "64") (name "U3_DQ9") (class "Default")
      (node (ref "U3") (pin "C3") (pinfunction "DQ9_C3") (pintype "bidirectional"))
    )
    (net (code "65") (name "U3_DQ10") (class "Default")
      (node (ref "U3") (pin "C8") (pinfunction "DQ10_C8") (pintype "bidirectional"))
    )
    (net (code "66") (name "U3_DQ11") (class "Default")
      (node (ref "U3") (pin "C2") (pinfunction "DQ11_C2") (pintype "bidirectional"))
    )
    (net (code "67") (name "U3_DQ12") (class "Default")
      (node (ref "U3") (pin "A7") (pinfunction "DQ12_A7") (pintype "bidirectional"))
    )
    (net (code "68") (name "U3_DQ13") (class "Default")
      (node (ref "U3") (pin "A2") (pinfunction "DQ13_A2") (pintype "bidirectional"))
    )
    (net (code "69") (name "U3_DQ14") (class "Default")
      (node (ref "U3") (pin "B8") (pinfunction "DQ14_B8") (pintype "bidirectional"))
    )
    (net (code "70") (name "U3_DQ15") (class "Default")
      (node (ref "U3") (pin "A3") (pinfunction "DQ15_A3") (pintype "bidirectional"))
    )
    (net (code "71") (name "U3_LDM") (class "Default")
      (node (ref "U3") (pin "E7") (pinfunction "LDM_E7") (pintype "input"))
    )
    (net (code "72") (name "U3_LDQS_N") (class "Default")
      (node (ref "U3") (pin "G3") (pinfunction "~{LDQS}_G3") (pintype "bidirectional"))
    )
    (net (code "73") (name "U3_LDQS_P") (class "Default")
      (node (ref "U3") (pin "F3") (pinfunction "LDQS_F3") (pintype "bidirectional"))
    )
    (net (code "74") (name "U3_ODT") (class "Default")
      (node (ref "U3") (pin "K1") (pinfunction "ODT_K1") (pintype "input"))
    )
    (net (code "75") (name "U3_UDM") (class "Default")
      (node (ref "U3") (pin "D3") (pinfunction "UDM_D3") (pintype "input"))
    )
    (net (code "76") (name "U3_UDQS_N") (class "Default")
      (node (ref "U3") (pin "B7") (pinfunction "~{UDQS}_B7") (pintype "bidirectional"))
    )
    (net (code "77") (name "U3_UDQS_P") (class "Default")
      (node (ref "U3") (pin "C7") (pinfunction "UDQS_C7") (pintype "bidirectional"))
    )
    (net (code "78") (name "U3_~{CAS}") (class "Default")
      (node (ref "U3") (pin "K3") (pinfunction "~{CAS}_K3") (pintype "input"))
    )
    (net (code "79") (name "U3_~{CS}") (class "Default")
      (node (ref "U3") (pin "L2") (pinfunction "~{CS}_L2") (pintype "input"))
    )
    (net (code "80") (name "U3_~{RAS}") (class "Default")
      (node (ref "U3") (pin "J3") (pinfunction "~{RAS}_J3") (pintype "input"))
    )
    (net (code "81") (name "U3_~{RESET}") (class "Default")
      (node (ref "U3") (pin "T2") (pinfunction "~{RESET}_T2") (pintype "input"))
    )
    (net (code "82") (name "U3_~{WE}") (class "Default")
      (node (ref "U3") (pin "L3") (pinfunction "~{WE}_L3") (pintype "input"))
    )
    (net (code "83") (name "VCCADC_0") (class "Default")
      (node (ref "U1") (pin "G8") (pinfunction "VCCADC_0_G8") (pintype "power_in"))
    )
    (net (code "84") (name "VREFN_0") (class "Default")
      (node (ref "U1") (pin "H7") (pinfunction "VREFN_0_H7") (pintype "power_in"))
    )
    (net (code "85") (name "VREFP_0") (class "Default")
      (node (ref "U1") (pin "J8") (pinfunction "VREFP_0_J8") (pintype "power_in"))
    )
    (net (code "86") (name "WP") (class "Default")
      (node (ref "R5") (pin "1") (pinfunction "1_1") (pintype "passive"))
      (node (ref "U1") (pin "K15") (pinfunction "IO_L2P_T0_D02_14_K15") (pintype "bidirectional"))
      (node (ref "U2") (pin "3") (pinfunction "WP_3") (pintype "bidirectional"))
    )
    (net (code "87") (name "unconnected-(U1B-DONE_0-PadH10)") (class "Default")
      (node (ref "U1") (pin "H10") (pinfunction "DONE_0_H10") (pintype "bidirectional"))
    )
    (net (code "88") (name "unconnected-(U1C-VN_0-PadJ7)") (class "Default")
      (node (ref "U1") (pin "J7") (pinfunction "VN_0_J7") (pintype "input"))
    )
    (net (code "89") (name "unconnected-(U1C-VP_0-PadH8)") (class "Default")
      (node (ref "U1") (pin "H8") (pinfunction "VP_0_H8") (pintype "input"))
    )
    (net (code "90") (name "unconnected-(U1D-IO_0_14-PadK12)") (class "Default")
      (node (ref "U1") (pin "K12") (pinfunction "IO_0_14_K12") (pintype "bidirectional"))
    )
    (net (code "91") (name "unconnected-(U1D-IO_25_14-PadP6)") (class "Default")
      (node (ref "U1") (pin "P6") (pinfunction "IO_25_14_P6") (pintype "bidirectional"))
    )
    (net (code "92") (name "unconnected-(U1D-IO_L3N_T0_DQS_EMCCLK_14-PadM15)") (class "Default")
      (node (ref "U1") (pin "M15") (pinfunction "IO_L3N_T0_DQS_EMCCLK_14_M15") (pintype "bidirectional"))
    )
    (net (code "93") (name "unconnected-(U1D-IO_L4N_T0_D05_14-PadM14)") (class "Default")
      (node (ref "U1") (pin "M14") (pinfunction "IO_L4N_T0_D05_14_M14") (pintype "bidirectional"))
    )
    (net (code "94") (name "unconnected-(U1D-IO_L4P_T0_D04_14-PadL14)") (class "Default")
      (node (ref "U1") (pin "L14") (pinfunction "IO_L4P_T0_D04_14_L14") (pintype "bidirectional"))
    )
    (net (code "95") (name "unconnected-(U1D-IO_L5N_T0_D07_14-PadL13)") (class "Default")
      (node (ref "U1") (pin "L13") (pinfunction "IO_L5N_T0_D07_14_L13") (pintype "bidirectional"))
    )
    (net (code "96") (name "unconnected-(U1D-IO_L5P_T0_D06_14-PadK13)") (class "Default")
      (node (ref "U1") (pin "K13") (pinfunction "IO_L5P_T0_D06_14_K13") (pintype "bidirectional"))
    )
    (net (code "97") (name "unconnected-(U1D-IO_L6N_T0_D08_VREF_14-PadM12)") (class "Default")
      (node (ref "U1") (pin "M12") (pinfunction "IO_L6N_T0_D08_VREF_14_M12") (pintype "bidirectional"))
    )
    (net (code "98") (name "unconnected-(U1D-IO_L7N_T1_D10_14-PadN16)") (class "Default")
      (node (ref "U1") (pin "N16") (pinfunction "IO_L7N_T1_D10_14_N16") (pintype "bidirectional"))
    )
    (net (code "99") (name "unconnected-(U1D-IO_L7P_T1_D09_14-PadM16)") (class "Default")
      (node (ref "U1") (pin "M16") (pinfunction "IO_L7P_T1_D09_14_M16") (pintype "bidirectional"))
    )
    (net (code "100") (name "unconnected-(U1D-IO_L8N_T1_D12_14-PadP16)") (class "Default")
      (node (ref "U1") (pin "P16") (pinfunction "IO_L8N_T1_D12_14_P16") (pintype "bidirectional"))
    )
    (net (code "101") (name "unconnected-(U1D-IO_L8P_T1_D11_14-PadP15)") (class "Default")
      (node (ref "U1") (pin "P15") (pinfunction "IO_L8P_T1_D11_14_P15") (pintype "bidirectional"))
    )
    (net (code "102") (name "unconnected-(U1D-IO_L9N_T1_DQS_D13_14-PadR16)") (class "Default")
      (node (ref "U1") (pin "R16") (pinfunction "IO_L9N_T1_DQS_D13_14_R16") (pintype "bidirectional"))
    )
    (net (code "103") (name "unconnected-(U1D-IO_L9P_T1_DQS_14-PadR15)") (class "Default")
      (node (ref "U1") (pin "R15") (pinfunction "IO_L9P_T1_DQS_14_R15") (pintype "bidirectional"))
    )
    (net (code "104") (name "unconnected-(U1D-IO_L10N_T1_D15_14-PadT15)") (class "Default")
      (node (ref "U1") (pin "T15") (pinfunction "IO_L10N_T1_D15_14_T15") (pintype "bidirectional"))
    )
    (net (code "105") (name "unconnected-(U1D-IO_L10P_T1_D14_14-PadT14)") (class "Default")
      (node (ref "U1") (pin "T14") (pinfunction "IO_L10P_T1_D14_14_T14") (pintype "bidirectional"))
    )
    (net (code "106") (name "unconnected-(U1D-IO_L11N_T1_SRCC_14-PadP13)") (class "Default")
      (node (ref "U1") (pin "P13") (pinfunction "IO_L11N_T1_SRCC_14_P13") (pintype "bidirectional"))
    )
    (net (code "107") (name "unconnected-(U1D-IO_L11P_T1_SRCC_14-PadN13)") (class "Default")
      (node (ref "U1") (pin "N13") (pinfunction "IO_L11P_T1_SRCC_14_N13") (pintype "bidirectional"))
    )
    (net (code "108") (name "unconnected-(U1D-IO_L12N_T1_MRCC_14-PadP14)") (class "Default")
      (node (ref "U1") (pin "P14") (pinfunction "IO_L12N_T1_MRCC_14_P14") (pintype "bidirectional"))
    )
    (net (code "109") (name "unconnected-(U1D-IO_L12P_T1_MRCC_14-PadN14)") (class "Default")
      (node (ref "U1") (pin "N14") (pinfunction "IO_L12P_T1_MRCC_14_N14") (pintype "bidirectional"))
    )
    (net (code "110") (name "unconnected-(U1D-IO_L13N_T2_MRCC_14-PadN12)") (class "Default")
      (node (ref "U1") (pin "N12") (pinfunction "IO_L13N_T2_MRCC_14_N12") (pintype "bidirectional"))
    )
    (net (code "111") (name "unconnected-(U1D-IO_L13P_T2_MRCC_14-PadN11)") (class "Default")
      (node (ref "U1") (pin "N11") (pinfunction "IO_L13P_T2_MRCC_14_N11") (pintype "bidirectional"))
    )
    (net (code "112") (name "unconnected-(U1D-IO_L14N_T2_SRCC_14-PadP11)") (class "Default")
      (node (ref "U1") (pin "P11") (pinfunction "IO_L14N_T2_SRCC_14_P11") (pintype "bidirectional"))
    )
    (net (code "113") (name "unconnected-(U1D-IO_L14P_T2_SRCC_14-PadP10)") (class "Default")
      (node (ref "U1") (pin "P10") (pinfunction "IO_L14P_T2_SRCC_14_P10") (pintype "bidirectional"))
    )
    (net (code "114") (name "unconnected-(U1D-IO_L15N_T2_DQS_DOUT_CSO_B_14-PadT12)") (class "Default")
      (node (ref "U1") (pin "T12") (pinfunction "IO_L15N_T2_DQS_DOUT_CSO_B_14_T12") (pintype "bidirectional"))
    )
    (net (code "115") (name "unconnected-(U1D-IO_L15P_T2_DQS_RDWR_B_14-PadR12)") (class "Default")
      (node (ref "U1") (pin "R12") (pinfunction "IO_L15P_T2_DQS_RDWR_B_14_R12") (pintype "bidirectional"))
    )
    (net (code "116") (name "unconnected-(U1D-IO_L16N_T2_A15_D31_14-PadT13)") (class "Default")
      (node (ref "U1") (pin "T13") (pinfunction "IO_L16N_T2_A15_D31_14_T13") (pintype "bidirectional"))
    )
    (net (code "117") (name "unconnected-(U1D-IO_L16P_T2_CSI_B_14-PadR13)") (class "Default")
      (node (ref "U1") (pin "R13") (pinfunction "IO_L16P_T2_CSI_B_14_R13") (pintype "bidirectional"))
    )
    (net (code "118") (name "unconnected-(U1D-IO_L17N_T2_A13_D29_14-PadR11)") (class "Default")
      (node (ref "U1") (pin "R11") (pinfunction "IO_L17N_T2_A13_D29_14_R11") (pintype "bidirectional"))
    )
    (net (code "119") (name "unconnected-(U1D-IO_L17P_T2_A14_D30_14-PadR10)") (class "Default")
      (node (ref "U1") (pin "R10") (pinfunction "IO_L17P_T2_A14_D30_14_R10") (pintype "bidirectional"))
    )
    (net (code "120") (name "unconnected-(U1D-IO_L18N_T2_A11_D27_14-PadP9)") (class "Default")
      (node (ref "U1") (pin "P9") (pinfunction "IO_L18N_T2_A11_D27_14_P9") (pintype "bidirectional"))
    )
    (net (code "121") (name "unconnected-(U1D-IO_L18P_T2_A12_D28_14-PadN9)") (class "Default")
      (node (ref "U1") (pin "N9") (pinfunction "IO_L18P_T2_A12_D28_14_N9") (pintype "bidirectional"))
    )
    (net (code "122") (name "unconnected-(U1D-IO_L19N_T3_A09_D25_VREF_14-PadN6)") (class "Default")
      (node (ref "U1") (pin "N6") (pinfunction "IO_L19N_T3_A09_D25_VREF_14_N6") (pintype "bidirectional"))
    )
    (net (code "123") (name "unconnected-(U1D-IO_L19P_T3_A10_D26_14-PadM6)") (class "Default")
      (node (ref "U1") (pin "M6") (pinfunction "IO_L19P_T3_A10_D26_14_M6") (pintype "bidirectional"))
    )
    (net (code "124") (name "unconnected-(U1D-IO_L20N_T3_A07_D23_14-PadR8)") (class "Default")
      (node (ref "U1") (pin "R8") (pinfunction "IO_L20N_T3_A07_D23_14_R8") (pintype "bidirectional"))
    )
    (net (code "125") (name "unconnected-(U1D-IO_L20P_T3_A08_D24_14-PadP8)") (class "Default")
      (node (ref "U1") (pin "P8") (pinfunction "IO_L20P_T3_A08_D24_14_P8") (pintype "bidirectional"))
    )
    (net (code "126") (name "unconnected-(U1D-IO_L21N_T3_DQS_A06_D22_14-PadT8)") (class "Default")
      (node (ref "U1") (pin "T8") (pinfunction "IO_L21N_T3_DQS_A06_D22_14_T8") (pintype "bidirectional"))
    )
    (net (code "127") (name "unconnected-(U1D-IO_L21P_T3_DQS_14-PadT7)") (class "Default")
      (node (ref "U1") (pin "T7") (pinfunction "IO_L21P_T3_DQS_14_T7") (pintype "bidirectional"))
    )
    (net (code "128") (name "unconnected-(U1D-IO_L22N_T3_A04_D20_14-PadT10)") (class "Default")
      (node (ref "U1") (pin "T10") (pinfunction "IO_L22N_T3_A04_D20_14_T10") (pintype "bidirectional"))
    )
    (net (code "129") (name "unconnected-(U1D-IO_L22P_T3_A05_D21_14-PadT9)") (class "Default")
      (node (ref "U1") (pin "T9") (pinfunction "IO_L22P_T3_A05_D21_14_T9") (pintype "bidirectional"))
    )
    (net (code "130") (name "unconnected-(U1D-IO_L23N_T3_A02_D18_14-PadT5)") (class "Default")
      (node (ref "U1") (pin "T5") (pinfunction "IO_L23N_T3_A02_D18_14_T5") (pintype "bidirectional"))
    )
    (net (code "131") (name "unconnected-(U1D-IO_L23P_T3_A03_D19_14-PadR5)") (class "Default")
      (node (ref "U1") (pin "R5") (pinfunction "IO_L23P_T3_A03_D19_14_R5") (pintype "bidirectional"))
    )
    (net (code "132") (name "unconnected-(U1D-IO_L24N_T3_A00_D16_14-PadR7)") (class "Default")
      (node (ref "U1") (pin "R7") (pinfunction "IO_L24N_T3_A00_D16_14_R7") (pintype "bidirectional"))
    )
    (net (code "133") (name "unconnected-(U1D-IO_L24P_T3_A01_D17_14-PadR6)") (class "Default")
      (node (ref "U1") (pin "R6") (pinfunction "IO_L24P_T3_A01_D17_14_R6") (pintype "bidirectional"))
    )
    (net (code "134") (name "unconnected-(U1E-IO_0_15-PadD10)") (class "Default")
      (node (ref "U1") (pin "D10") (pinfunction "IO_0_15_D10") (pintype "bidirectional"))
    )
    (net (code "135") (name "unconnected-(U1E-IO_25_15-PadG11)") (class "Default")
      (node (ref "U1") (pin "G11") (pinfunction "IO_25_15_G11") (pintype "bidirectional"))
    )
    (net (code "136") (name "unconnected-(U1E-IO_L1N_T0_AD0N_15-PadC9)") (class "Default")
      (node (ref "U1") (pin "C9") (pinfunction "IO_L1N_T0_AD0N_15_C9") (pintype "bidirectional"))
    )
    (net (code "137") (name "unconnected-(U1E-IO_L1P_T0_AD0P_15-PadC8)") (class "Default")
      (node (ref "U1") (pin "C8") (pinfunction "IO_L1P_T0_AD0P_15_C8") (pintype "bidirectional"))
    )
    (net (code "138") (name "unconnected-(U1E-IO_L2N_T0_AD8N_15-PadA9)") (class "Default")
      (node (ref "U1") (pin "A9") (pinfunction "IO_L2N_T0_AD8N_15_A9") (pintype "bidirectional"))
    )
    (net (code "139") (name "unconnected-(U1E-IO_L2P_T0_AD8P_15-PadA8)") (class "Default")
      (node (ref "U1") (pin "A8") (pinfunction "IO_L2P_T0_AD8P_15_A8") (pintype "bidirectional"))
    )
    (net (code "140") (name "unconnected-(U1E-IO_L3N_T0_DQS_AD1N_15-PadA10)") (class "Default")
      (node (ref "U1") (pin "A10") (pinfunction "IO_L3N_T0_DQS_AD1N_15_A10") (pintype "bidirectional"))
    )
    (net (code "141") (name "unconnected-(U1E-IO_L3P_T0_DQS_AD1P_15-PadB9)") (class "Default")
      (node (ref "U1") (pin "B9") (pinfunction "IO_L3P_T0_DQS_AD1P_15_B9") (pintype "bidirectional"))
    )
    (net (code "142") (name "unconnected-(U1E-IO_L4N_T0_15-PadB11)") (class "Default")
      (node (ref "U1") (pin "B11") (pinfunction "IO_L4N_T0_15_B11") (pintype "bidirectional"))
    )
    (net (code "143") (name "unconnected-(U1E-IO_L4P_T0_15-PadB10)") (class "Default")
      (node (ref "U1") (pin "B10") (pinfunction "IO_L4P_T0_15_B10") (pintype "bidirectional"))
    )
    (net (code "144") (name "unconnected-(U1E-IO_L5N_T0_AD9N_15-PadA12)") (class "Default")
      (node (ref "U1") (pin "A12") (pinfunction "IO_L5N_T0_AD9N_15_A12") (pintype "bidirectional"))
    )
    (net (code "145") (name "unconnected-(U1E-IO_L5P_T0_AD9P_15-PadB12)") (class "Default")
      (node (ref "U1") (pin "B12") (pinfunction "IO_L5P_T0_AD9P_15_B12") (pintype "bidirectional"))
    )
    (net (code "146") (name "unconnected-(U1E-IO_L6N_T0_VREF_15-PadD9)") (class "Default")
      (node (ref "U1") (pin "D9") (pinfunction "IO_L6N_T0_VREF_15_D9") (pintype "bidirectional"))
    )
    (net (code "147") (name "unconnected-(U1E-IO_L6P_T0_15-PadD8)") (class "Default")
      (node (ref "U1") (pin "D8") (pinfunction "IO_L6P_T0_15_D8") (pintype "bidirectional"))
    )
    (net (code "148") (name "unconnected-(U1E-IO_L7N_T1_AD2N_15-PadA14)") (class "Default")
      (node (ref "U1") (pin "A14") (pinfunction "IO_L7N_T1_AD2N_15_A14") (pintype "bidirectional"))
    )
    (net (code "149") (name "unconnected-(U1E-IO_L7P_T1_AD2P_15-PadA13)") (class "Default")
      (node (ref "U1") (pin "A13") (pinfunction "IO_L7P_T1_AD2P_15_A13") (pintype "bidirectional"))
    )
    (net (code "150") (name "unconnected-(U1E-IO_L8N_T1_AD10N_15-PadB14)") (class "Default")
      (node (ref "U1") (pin "B14") (pinfunction "IO_L8N_T1_AD10N_15_B14") (pintype "bidirectional"))
    )
    (net (code "151") (name "unconnected-(U1E-IO_L8P_T1_AD10P_15-PadC14)") (class "Default")
      (node (ref "U1") (pin "C14") (pinfunction "IO_L8P_T1_AD10P_15_C14") (pintype "bidirectional"))
    )
    (net (code "152") (name "unconnected-(U1E-IO_L9N_T1_DQS_AD3N_15-PadA15)") (class "Default")
      (node (ref "U1") (pin "A15") (pinfunction "IO_L9N_T1_DQS_AD3N_15_A15") (pintype "bidirectional"))
    )
    (net (code "153") (name "unconnected-(U1E-IO_L9P_T1_DQS_AD3P_15-PadB15)") (class "Default")
      (node (ref "U1") (pin "B15") (pinfunction "IO_L9P_T1_DQS_AD3P_15_B15") (pintype "bidirectional"))
    )
    (net (code "154") (name "unconnected-(U1E-IO_L10N_T1_AD11N_15-PadB16)") (class "Default")
      (node (ref "U1") (pin "B16") (pinfunction "IO_L10N_T1_AD11N_15_B16") (pintype "bidirectional"))
    )
    (net (code "155") (name "unconnected-(U1E-IO_L10P_T1_AD11P_15-PadC16)") (class "Default")
      (node (ref "U1") (pin "C16") (pinfunction "IO_L10P_T1_AD11P_15_C16") (pintype "bidirectional"))
    )
    (net (code "156") (name "unconnected-(U1E-IO_L11N_T1_SRCC_15-PadC12)") (class "Default")
      (node (ref "U1") (pin "C12") (pinfunction "IO_L11N_T1_SRCC_15_C12") (pintype "bidirectional"))
    )
    (net (code "157") (name "unconnected-(U1E-IO_L11P_T1_SRCC_15-PadC11)") (class "Default")
      (node (ref "U1") (pin "C11") (pinfunction "IO_L11P_T1_SRCC_15_C11") (pintype "bidirectional"))
    )
    (net (code "158") (name "unconnected-(U1E-IO_L12N_T1_MRCC_15-PadC13)") (class "Default")
      (node (ref "U1") (pin "C13") (pinfunction "IO_L12N_T1_MRCC_15_C13") (pintype "bidirectional"))
    )
    (net (code "159") (name "unconnected-(U1E-IO_L12P_T1_MRCC_15-PadD13)") (class "Default")
      (node (ref "U1") (pin "D13") (pinfunction "IO_L12P_T1_MRCC_15_D13") (pintype "bidirectional"))
    )
    (net (code "160") (name "unconnected-(U1E-IO_L13N_T2_MRCC_15-PadE13)") (class "Default")
      (node (ref "U1") (pin "E13") (pinfunction "IO_L13N_T2_MRCC_15_E13") (pintype "bidirectional"))
    )
    (net (code "161") (name "unconnected-(U1E-IO_L13P_T2_MRCC_15-PadE12)") (class "Default")
      (node (ref "U1") (pin "E12") (pinfunction "IO_L13P_T2_MRCC_15_E12") (pintype "bidirectional"))
    )
    (net (code "162") (name "unconnected-(U1E-IO_L14N_T2_SRCC_15-PadD11)") (class "Default")
      (node (ref "U1") (pin "D11") (pinfunction "IO_L14N_T2_SRCC_15_D11") (pintype "bidirectional"))
    )
    (net (code "163") (name "unconnected-(U1E-IO_L14P_T2_SRCC_15-PadE11)") (class "Default")
      (node (ref "U1") (pin "E11") (pinfunction "IO_L14P_T2_SRCC_15_E11") (pintype "bidirectional"))
    )
    (net (code "164") (name "unconnected-(U1E-IO_L15N_T2_DQS_ADV_B_15-PadD15)") (class "Default")
      (node (ref "U1") (pin "D15") (pinfunction "IO_L15N_T2_DQS_ADV_B_15_D15") (pintype "bidirectional"))
    )
    (net (code "165") (name "unconnected-(U1E-IO_L15P_T2_DQS_15-PadD14)") (class "Default")
      (node (ref "U1") (pin "D14") (pinfunction "IO_L15P_T2_DQS_15_D14") (pintype "bidirectional"))
    )
    (net (code "166") (name "unconnected-(U1E-IO_L16N_T2_A27_15-PadF13)") (class "Default")
      (node (ref "U1") (pin "F13") (pinfunction "IO_L16N_T2_A27_15_F13") (pintype "bidirectional"))
    )
    (net (code "167") (name "unconnected-(U1E-IO_L16P_T2_A28_15-PadF12)") (class "Default")
      (node (ref "U1") (pin "F12") (pinfunction "IO_L16P_T2_A28_15_F12") (pintype "bidirectional"))
    )
    (net (code "168") (name "unconnected-(U1E-IO_L17N_T2_A25_15-PadD16)") (class "Default")
      (node (ref "U1") (pin "D16") (pinfunction "IO_L17N_T2_A25_15_D16") (pintype "bidirectional"))
    )
    (net (code "169") (name "unconnected-(U1E-IO_L17P_T2_A26_15-PadE16)") (class "Default")
      (node (ref "U1") (pin "E16") (pinfunction "IO_L17P_T2_A26_15_E16") (pintype "bidirectional"))
    )
    (net (code "170") (name "unconnected-(U1E-IO_L18N_T2_A23_15-PadE15)") (class "Default")
      (node (ref "U1") (pin "E15") (pinfunction "IO_L18N_T2_A23_15_E15") (pintype "bidirectional"))
    )
    (net (code "171") (name "unconnected-(U1E-IO_L18P_T2_A24_15-PadF15)") (class "Default")
      (node (ref "U1") (pin "F15") (pinfunction "IO_L18P_T2_A24_15_F15") (pintype "bidirectional"))
    )
    (net (code "172") (name "unconnected-(U1E-IO_L19N_T3_A21_VREF_15-PadG12)") (class "Default")
      (node (ref "U1") (pin "G12") (pinfunction "IO_L19N_T3_A21_VREF_15_G12") (pintype "bidirectional"))
    )
    (net (code "173") (name "unconnected-(U1E-IO_L19P_T3_A22_15-PadH11)") (class "Default")
      (node (ref "U1") (pin "H11") (pinfunction "IO_L19P_T3_A22_15_H11") (pintype "bidirectional"))
    )
    (net (code "174") (name "unconnected-(U1E-IO_L20N_T3_A19_15-PadH13)") (class "Default")
      (node (ref "U1") (pin "H13") (pinfunction "IO_L20N_T3_A19_15_H13") (pintype "bidirectional"))
    )
    (net (code "175") (name "unconnected-(U1E-IO_L20P_T3_A20_15-PadH12)") (class "Default")
      (node (ref "U1") (pin "H12") (pinfunction "IO_L20P_T3_A20_15_H12") (pintype "bidirectional"))
    )
    (net (code "176") (name "unconnected-(U1E-IO_L21N_T3_DQS_A18_15-PadF14)") (class "Default")
      (node (ref "U1") (pin "F14") (pinfunction "IO_L21N_T3_DQS_A18_15_F14") (pintype "bidirectional"))
    )
    (net (code "177") (name "unconnected-(U1E-IO_L21P_T3_DQS_15-PadG14)") (class "Default")
      (node (ref "U1") (pin "G14") (pinfunction "IO_L21P_T3_DQS_15_G14") (pintype "bidirectional"))
    )
    (net (code "178") (name "unconnected-(U1E-IO_L22N_T3_A16_15-PadG16)") (class "Default")
      (node (ref "U1") (pin "G16") (pinfunction "IO_L22N_T3_A16_15_G16") (pintype "bidirectional"))
    )
    (net (code "179") (name "unconnected-(U1E-IO_L22P_T3_A17_15-PadH16)") (class "Default")
      (node (ref "U1") (pin "H16") (pinfunction "IO_L22P_T3_A17_15_H16") (pintype "bidirectional"))
    )
    (net (code "180") (name "unconnected-(U1E-IO_L23N_T3_FWE_B_15-PadJ16)") (class "Default")
      (node (ref "U1") (pin "J16") (pinfunction "IO_L23N_T3_FWE_B_15_J16") (pintype "bidirectional"))
    )
    (net (code "181") (name "unconnected-(U1E-IO_L23P_T3_FOE_B_15-PadJ15)") (class "Default")
      (node (ref "U1") (pin "J15") (pinfunction "IO_L23P_T3_FOE_B_15_J15") (pintype "bidirectional"))
    )
    (net (code "182") (name "unconnected-(U1E-IO_L24N_T3_RS0_15-PadG15)") (class "Default")
      (node (ref "U1") (pin "G15") (pinfunction "IO_L24N_T3_RS0_15_G15") (pintype "bidirectional"))
    )
    (net (code "183") (name "unconnected-(U1E-IO_L24P_T3_RS1_15-PadH14)") (class "Default")
      (node (ref "U1") (pin "H14") (pinfunction "IO_L24P_T3_RS1_15_H14") (pintype "bidirectional"))
    )
    (net (code "184") (name "unconnected-(U1F-IO_0_34-PadL5)") (class "Default")
      (node (ref "U1") (pin "L5") (pinfunction "IO_0_34_L5") (pintype "bidirectional"))
    )
    (net (code "185") (name "unconnected-(U1F-IO_L1N_T0_34-PadL4)") (class "Default")
      (node (ref "U1") (pin "L4") (pinfunction "IO_L1N_T0_34_L4") (pintype "bidirectional"))
    )
    (net (code "186") (name "unconnected-(U1F-IO_L1P_T0_34-PadM4)") (class "Default")
      (node (ref "U1") (pin "M4") (pinfunction "IO_L1P_T0_34_M4") (pintype "bidirectional"))
    )
    (net (code "187") (name "unconnected-(U1F-IO_L2N_T0_34-PadM1)") (class "Default")
      (node (ref "U1") (pin "M1") (pinfunction "IO_L2N_T0_34_M1") (pintype "bidirectional"))
    )
    (net (code "188") (name "unconnected-(U1F-IO_L2P_T0_34-PadM2)") (class "Default")
      (node (ref "U1") (pin "M2") (pinfunction "IO_L2P_T0_34_M2") (pintype "bidirectional"))
    )
    (net (code "189") (name "unconnected-(U1F-IO_L3N_T0_DQS_34-PadN2)") (class "Default")
      (node (ref "U1") (pin "N2") (pinfunction "IO_L3N_T0_DQS_34_N2") (pintype "bidirectional"))
    )
    (net (code "190") (name "unconnected-(U1F-IO_L3P_T0_DQS_34-PadN3)") (class "Default")
      (node (ref "U1") (pin "N3") (pinfunction "IO_L3P_T0_DQS_34_N3") (pintype "bidirectional"))
    )
    (net (code "191") (name "unconnected-(U1F-IO_L4N_T0_34-PadP1)") (class "Default")
      (node (ref "U1") (pin "P1") (pinfunction "IO_L4N_T0_34_P1") (pintype "bidirectional"))
    )
    (net (code "192") (name "unconnected-(U1F-IO_L4P_T0_34-PadN1)") (class "Default")
      (node (ref "U1") (pin "N1") (pinfunction "IO_L4P_T0_34_N1") (pintype "bidirectional"))
    )
    (net (code "193") (name "unconnected-(U1F-IO_L5N_T0_34-PadP3)") (class "Default")
      (node (ref "U1") (pin "P3") (pinfunction "IO_L5N_T0_34_P3") (pintype "bidirectional"))
    )
    (net (code "194") (name "unconnected-(U1F-IO_L5P_T0_34-PadP4)") (class "Default")
      (node (ref "U1") (pin "P4") (pinfunction "IO_L5P_T0_34_P4") (pintype "bidirectional"))
    )
    (net (code "195") (name "unconnected-(U1F-IO_L6N_T0_VREF_34-PadN4)") (class "Default")
      (node (ref "U1") (pin "N4") (pinfunction "IO_L6N_T0_VREF_34_N4") (pintype "bidirectional"))
    )
    (net (code "196") (name "unconnected-(U1F-IO_L6P_T0_34-PadM5)") (class "Default")
      (node (ref "U1") (pin "M5") (pinfunction "IO_L6P_T0_34_M5") (pintype "bidirectional"))
    )
    (net (code "197") (name "unconnected-(U1F-IO_L7N_T1_34-PadR1)") (class "Default")
      (node (ref "U1") (pin "R1") (pinfunction "IO_L7N_T1_34_R1") (pintype "bidirectional"))
    )
    (net (code "198") (name "unconnected-(U1F-IO_L7P_T1_34-PadR2)") (class "Default")
      (node (ref "U1") (pin "R2") (pinfunction "IO_L7P_T1_34_R2") (pintype "bidirectional"))
    )
    (net (code "199") (name "unconnected-(U1F-IO_L8N_T1_34-PadT2)") (class "Default")
      (node (ref "U1") (pin "T2") (pinfunction "IO_L8N_T1_34_T2") (pintype "bidirectional"))
    )
    (net (code "200") (name "unconnected-(U1F-IO_L8P_T1_34-PadR3)") (class "Default")
      (node (ref "U1") (pin "R3") (pinfunction "IO_L8P_T1_34_R3") (pintype "bidirectional"))
    )
    (net (code "201") (name "unconnected-(U1F-IO_L9N_T1_DQS_34-PadT3)") (class "Default")
      (node (ref "U1") (pin "T3") (pinfunction "IO_L9N_T1_DQS_34_T3") (pintype "bidirectional"))
    )
    (net (code "202") (name "unconnected-(U1F-IO_L9P_T1_DQS_34-PadT4)") (class "Default")
      (node (ref "U1") (pin "T4") (pinfunction "IO_L9P_T1_DQS_34_T4") (pintype "bidirectional"))
    )
    (net (code "203") (name "unconnected-(U1F-IO_L10P_T1_34-PadP5)") (class "Default")
      (node (ref "U1") (pin "P5") (pinfunction "IO_L10P_T1_34_P5") (pintype "bidirectional"))
    )
    (net (code "204") (name "unconnected-(U1G-IO_0_35-PadE6)") (class "Default")
      (node (ref "U1") (pin "E6") (pinfunction "IO_0_35_E6") (pintype "bidirectional"))
    )
    (net (code "205") (name "unconnected-(U1G-IO_25_35-PadK5)") (class "Default")
      (node (ref "U1") (pin "K5") (pinfunction "IO_25_35_K5") (pintype "bidirectional"))
    )
    (net (code "206") (name "unconnected-(U1G-IO_L1N_T0_AD4N_35-PadA7)") (class "Default")
      (node (ref "U1") (pin "A7") (pinfunction "IO_L1N_T0_AD4N_35_A7") (pintype "bidirectional"))
    )
    (net (code "207") (name "unconnected-(U1G-IO_L1P_T0_AD4P_35-PadB7)") (class "Default")
      (node (ref "U1") (pin "B7") (pinfunction "IO_L1P_T0_AD4P_35_B7") (pintype "bidirectional"))
    )
    (net (code "208") (name "unconnected-(U1G-IO_L2N_T0_AD12N_35-PadB5)") (class "Default")
      (node (ref "U1") (pin "B5") (pinfunction "IO_L2N_T0_AD12N_35_B5") (pintype "bidirectional"))
    )
    (net (code "209") (name "unconnected-(U1G-IO_L2P_T0_AD12P_35-PadB6)") (class "Default")
      (node (ref "U1") (pin "B6") (pinfunction "IO_L2P_T0_AD12P_35_B6") (pintype "bidirectional"))
    )
    (net (code "210") (name "unconnected-(U1G-IO_L3N_T0_DQS_AD5N_35-PadA4)") (class "Default")
      (node (ref "U1") (pin "A4") (pinfunction "IO_L3N_T0_DQS_AD5N_35_A4") (pintype "bidirectional"))
    )
    (net (code "211") (name "unconnected-(U1G-IO_L3P_T0_DQS_AD5P_35-PadA5)") (class "Default")
      (node (ref "U1") (pin "A5") (pinfunction "IO_L3P_T0_DQS_AD5P_35_A5") (pintype "bidirectional"))
    )
    (net (code "212") (name "unconnected-(U1G-IO_L4N_T0_35-PadA3)") (class "Default")
      (node (ref "U1") (pin "A3") (pinfunction "IO_L4N_T0_35_A3") (pintype "bidirectional"))
    )
    (net (code "213") (name "unconnected-(U1G-IO_L4P_T0_35-PadB4)") (class "Default")
      (node (ref "U1") (pin "B4") (pinfunction "IO_L4P_T0_35_B4") (pintype "bidirectional"))
    )
    (net (code "214") (name "unconnected-(U1G-IO_L5N_T0_AD13N_35-PadC6)") (class "Default")
      (node (ref "U1") (pin "C6") (pinfunction "IO_L5N_T0_AD13N_35_C6") (pintype "bidirectional"))
    )
    (net (code "215") (name "unconnected-(U1G-IO_L5P_T0_AD13P_35-PadC7)") (class "Default")
      (node (ref "U1") (pin "C7") (pinfunction "IO_L5P_T0_AD13P_35_C7") (pintype "bidirectional"))
    )
    (net (code "216") (name "unconnected-(U1G-IO_L6N_T0_VREF_35-PadD5)") (class "Default")
      (node (ref "U1") (pin "D5") (pinfunction "IO_L6N_T0_VREF_35_D5") (pintype "bidirectional"))
    )
    (net (code "217") (name "unconnected-(U1G-IO_L6P_T0_35-PadD6)") (class "Default")
      (node (ref "U1") (pin "D6") (pinfunction "IO_L6P_T0_35_D6") (pintype "bidirectional"))
    )
    (net (code "218") (name "unconnected-(U1G-IO_L7N_T1_AD6N_35-PadC2)") (class "Default")
      (node (ref "U1") (pin "C2") (pinfunction "IO_L7N_T1_AD6N_35_C2") (pintype "bidirectional"))
    )
    (net (code "219") (name "unconnected-(U1G-IO_L7P_T1_AD6P_35-PadC3)") (class "Default")
      (node (ref "U1") (pin "C3") (pinfunction "IO_L7P_T1_AD6P_35_C3") (pintype "bidirectional"))
    )
    (net (code "220") (name "unconnected-(U1G-IO_L8N_T1_AD14N_35-PadA2)") (class "Default")
      (node (ref "U1") (pin "A2") (pinfunction "IO_L8N_T1_AD14N_35_A2") (pintype "bidirectional"))
    )
    (net (code "221") (name "unconnected-(U1G-IO_L8P_T1_AD14P_35-PadB2)") (class "Default")
      (node (ref "U1") (pin "B2") (pinfunction "IO_L8P_T1_AD14P_35_B2") (pintype "bidirectional"))
    )
    (net (code "222") (name "unconnected-(U1G-IO_L9N_T1_DQS_AD7N_35-PadB1)") (class "Default")
      (node (ref "U1") (pin "B1") (pinfunction "IO_L9N_T1_DQS_AD7N_35_B1") (pintype "bidirectional"))
    )
    (net (code "223") (name "unconnected-(U1G-IO_L9P_T1_DQS_AD7P_35-PadC1)") (class "Default")
      (node (ref "U1") (pin "C1") (pinfunction "IO_L9P_T1_DQS_AD7P_35_C1") (pintype "bidirectional"))
    )
    (net (code "224") (name "unconnected-(U1G-IO_L10N_T1_AD15N_35-PadD1)") (class "Default")
      (node (ref "U1") (pin "D1") (pinfunction "IO_L10N_T1_AD15N_35_D1") (pintype "bidirectional"))
    )
    (net (code "225") (name "unconnected-(U1G-IO_L10P_T1_AD15P_35-PadE2)") (class "Default")
      (node (ref "U1") (pin "E2") (pinfunction "IO_L10P_T1_AD15P_35_E2") (pintype "bidirectional"))
    )
    (net (code "226") (name "unconnected-(U1G-IO_L11N_T1_SRCC_35-PadD3)") (class "Default")
      (node (ref "U1") (pin "D3") (pinfunction "IO_L11N_T1_SRCC_35_D3") (pintype "bidirectional"))
    )
    (net (code "227") (name "unconnected-(U1G-IO_L11P_T1_SRCC_35-PadE3)") (class "Default")
      (node (ref "U1") (pin "E3") (pinfunction "IO_L11P_T1_SRCC_35_E3") (pintype "bidirectional"))
    )
    (net (code "228") (name "unconnected-(U1G-IO_L12N_T1_MRCC_35-PadC4)") (class "Default")
      (node (ref "U1") (pin "C4") (pinfunction "IO_L12N_T1_MRCC_35_C4") (pintype "bidirectional"))
    )
    (net (code "229") (name "unconnected-(U1G-IO_L12P_T1_MRCC_35-PadD4)") (class "Default")
      (node (ref "U1") (pin "D4") (pinfunction "IO_L12P_T1_MRCC_35_D4") (pintype "bidirectional"))
    )
    (net (code "230") (name "unconnected-(U1G-IO_L13N_T2_MRCC_35-PadE5)") (class "Default")
      (node (ref "U1") (pin "E5") (pinfunction "IO_L13N_T2_MRCC_35_E5") (pintype "bidirectional"))
    )
    (net (code "231") (name "unconnected-(U1G-IO_L13P_T2_MRCC_35-PadF5)") (class "Default")
      (node (ref "U1") (pin "F5") (pinfunction "IO_L13P_T2_MRCC_35_F5") (pintype "bidirectional"))
    )
    (net (code "232") (name "unconnected-(U1G-IO_L14N_T2_SRCC_35-PadF3)") (class "Default")
      (node (ref "U1") (pin "F3") (pinfunction "IO_L14N_T2_SRCC_35_F3") (pintype "bidirectional"))
    )
    (net (code "233") (name "unconnected-(U1G-IO_L14P_T2_SRCC_35-PadF4)") (class "Default")
      (node (ref "U1") (pin "F4") (pinfunction "IO_L14P_T2_SRCC_35_F4") (pintype "bidirectional"))
    )
    (net (code "234") (name "unconnected-(U1G-IO_L15N_T2_DQS_35-PadE1)") (class "Default")
      (node (ref "U1") (pin "E1") (pinfunction "IO_L15N_T2_DQS_35_E1") (pintype "bidirectional"))
    )
    (net (code "235") (name "unconnected-(U1G-IO_L15P_T2_DQS_35-PadF2)") (class "Default")
      (node (ref "U1") (pin "F2") (pinfunction "IO_L15P_T2_DQS_35_F2") (pintype "bidirectional"))
    )
    (net (code "236") (name "unconnected-(U1G-IO_L16N_T2_35-PadG4)") (class "Default")
      (node (ref "U1") (pin "G4") (pinfunction "IO_L16N_T2_35_G4") (pintype "bidirectional"))
    )
    (net (code "237") (name "unconnected-(U1G-IO_L16P_T2_35-PadG5)") (class "Default")
      (node (ref "U1") (pin "G5") (pinfunction "IO_L16P_T2_35_G5") (pintype "bidirectional"))
    )
    (net (code "238") (name "unconnected-(U1G-IO_L17N_T2_35-PadG1)") (class "Default")
      (node (ref "U1") (pin "G1") (pinfunction "IO_L17N_T2_35_G1") (pintype "bidirectional"))
    )
    (net (code "239") (name "unconnected-(U1G-IO_L17P_T2_35-PadG2)") (class "Default")
      (node (ref "U1") (pin "G2") (pinfunction "IO_L17P_T2_35_G2") (pintype "bidirectional"))
    )
    (net (code "240") (name "unconnected-(U1G-IO_L18N_T2_35-PadH4)") (class "Default")
      (node (ref "U1") (pin "H4") (pinfunction "IO_L18N_T2_35_H4") (pintype "bidirectional"))
    )
    (net (code "241") (name "unconnected-(U1G-IO_L18P_T2_35-PadH5)") (class "Default")
      (node (ref "U1") (pin "H5") (pinfunction "IO_L18P_T2_35_H5") (pintype "bidirectional"))
    )
    (net (code "242") (name "unconnected-(U1G-IO_L19N_T3_VREF_35-PadJ4)") (class "Default")
      (node (ref "U1") (pin "J4") (pinfunction "IO_L19N_T3_VREF_35_J4") (pintype "bidirectional"))
    )
    (net (code "243") (name "unconnected-(U1G-IO_L19P_T3_35-PadJ5)") (class "Default")
      (node (ref "U1") (pin "J5") (pinfunction "IO_L19P_T3_35_J5") (pintype "bidirectional"))
    )
    (net (code "244") (name "unconnected-(U1G-IO_L20N_T3_35-PadH1)") (class "Default")
      (node (ref "U1") (pin "H1") (pinfunction "IO_L20N_T3_35_H1") (pintype "bidirectional"))
    )
    (net (code "245") (name "unconnected-(U1G-IO_L20P_T3_35-PadH2)") (class "Default")
      (node (ref "U1") (pin "H2") (pinfunction "IO_L20P_T3_35_H2") (pintype "bidirectional"))
    )
    (net (code "246") (name "unconnected-(U1G-IO_L21N_T3_DQS_35-PadH3)") (class "Default")
      (node (ref "U1") (pin "H3") (pinfunction "IO_L21N_T3_DQS_35_H3") (pintype "bidirectional"))
    )
    (net (code "247") (name "unconnected-(U1G-IO_L21P_T3_DQS_35-PadJ3)") (class "Default")
      (node (ref "U1") (pin "J3") (pinfunction "IO_L21P_T3_DQS_35_J3") (pintype "bidirectional"))
    )
    (net (code "248") (name "unconnected-(U1G-IO_L22N_T3_35-PadJ1)") (class "Default")
      (node (ref "U1") (pin "J1") (pinfunction "IO_L22N_T3_35_J1") (pintype "bidirectional"))
    )
    (net (code "249") (name "unconnected-(U1G-IO_L22P_T3_35-PadK1)") (class "Default")
      (node (ref "U1") (pin "K1") (pinfunction "IO_L22P_T3_35_K1") (pintype "bidirectional"))
    )
    (net (code "250") (name "unconnected-(U1G-IO_L23N_T3_35-PadL2)") (class "Default")
      (node (ref "U1") (pin "L2") (pinfunction "IO_L23N_T3_35_L2") (pintype "bidirectional"))
    )
    (net (code "251") (name "unconnected-(U1G-IO_L23P_T3_35-PadL3)") (class "Default")
      (node (ref "U1") (pin "L3") (pinfunction "IO_L23P_T3_35_L3") (pintype "bidirectional"))
    )
    (net (code "252") (name "unconnected-(U1G-IO_L24N_T3_35-PadK2)") (class "Default")
      (node (ref "U1") (pin "K2") (pinfunction "IO_L24N_T3_35_K2") (pintype "bidirectional"))
    )
    (net (code "253") (name "unconnected-(U1G-IO_L24P_T3_35-PadK3)") (class "Default")
      (node (ref "U1") (pin "K3") (pinfunction "IO_L24P_T3_35_K3") (pintype "bidirectional"))
    )
  )
)
